# TeensyAmp_R4_0.net
KiCad netlist of a schematic drawn in EAGLE
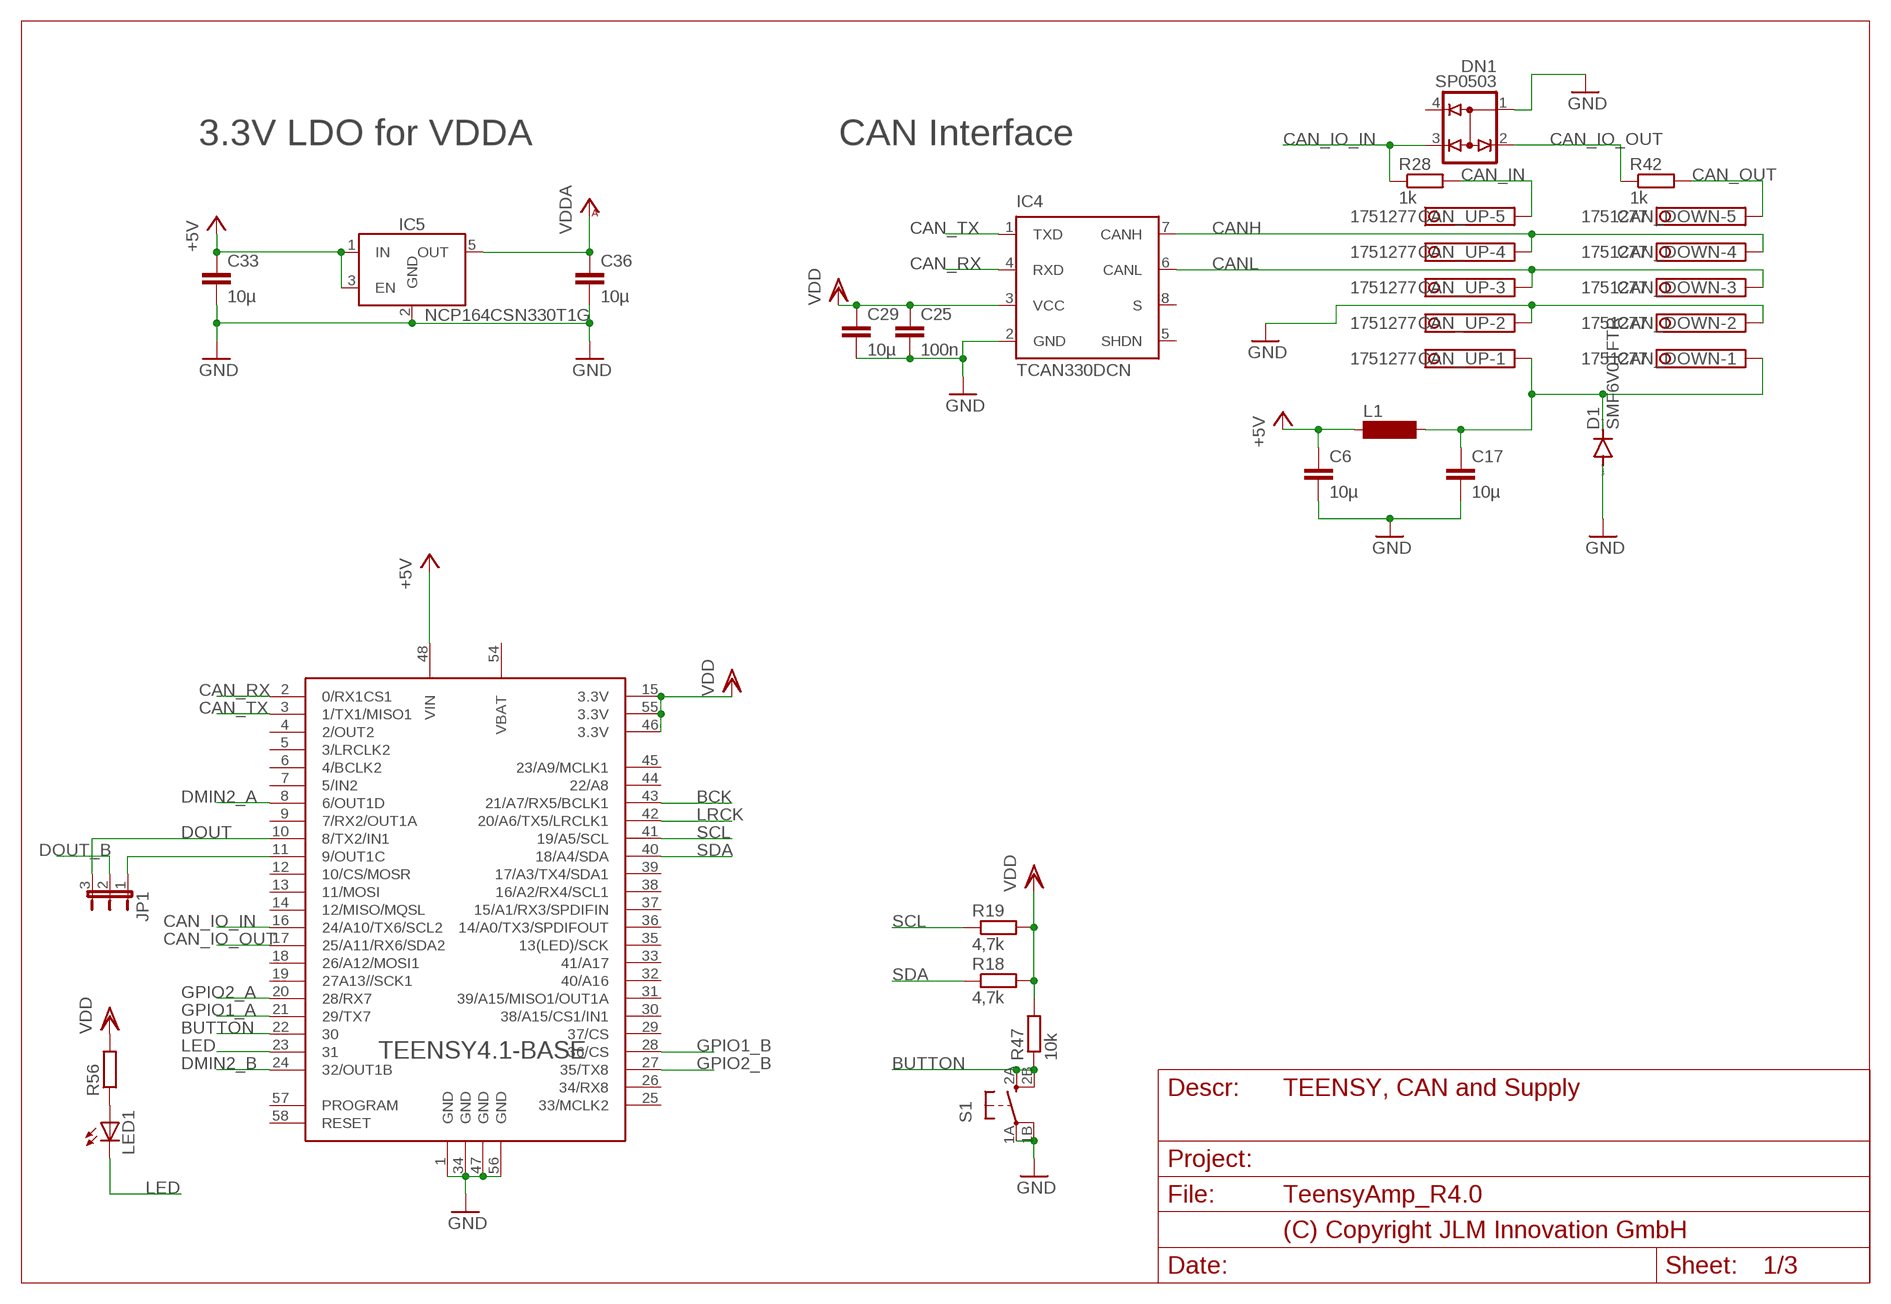
[diagram p0: schematic, sheet 1]
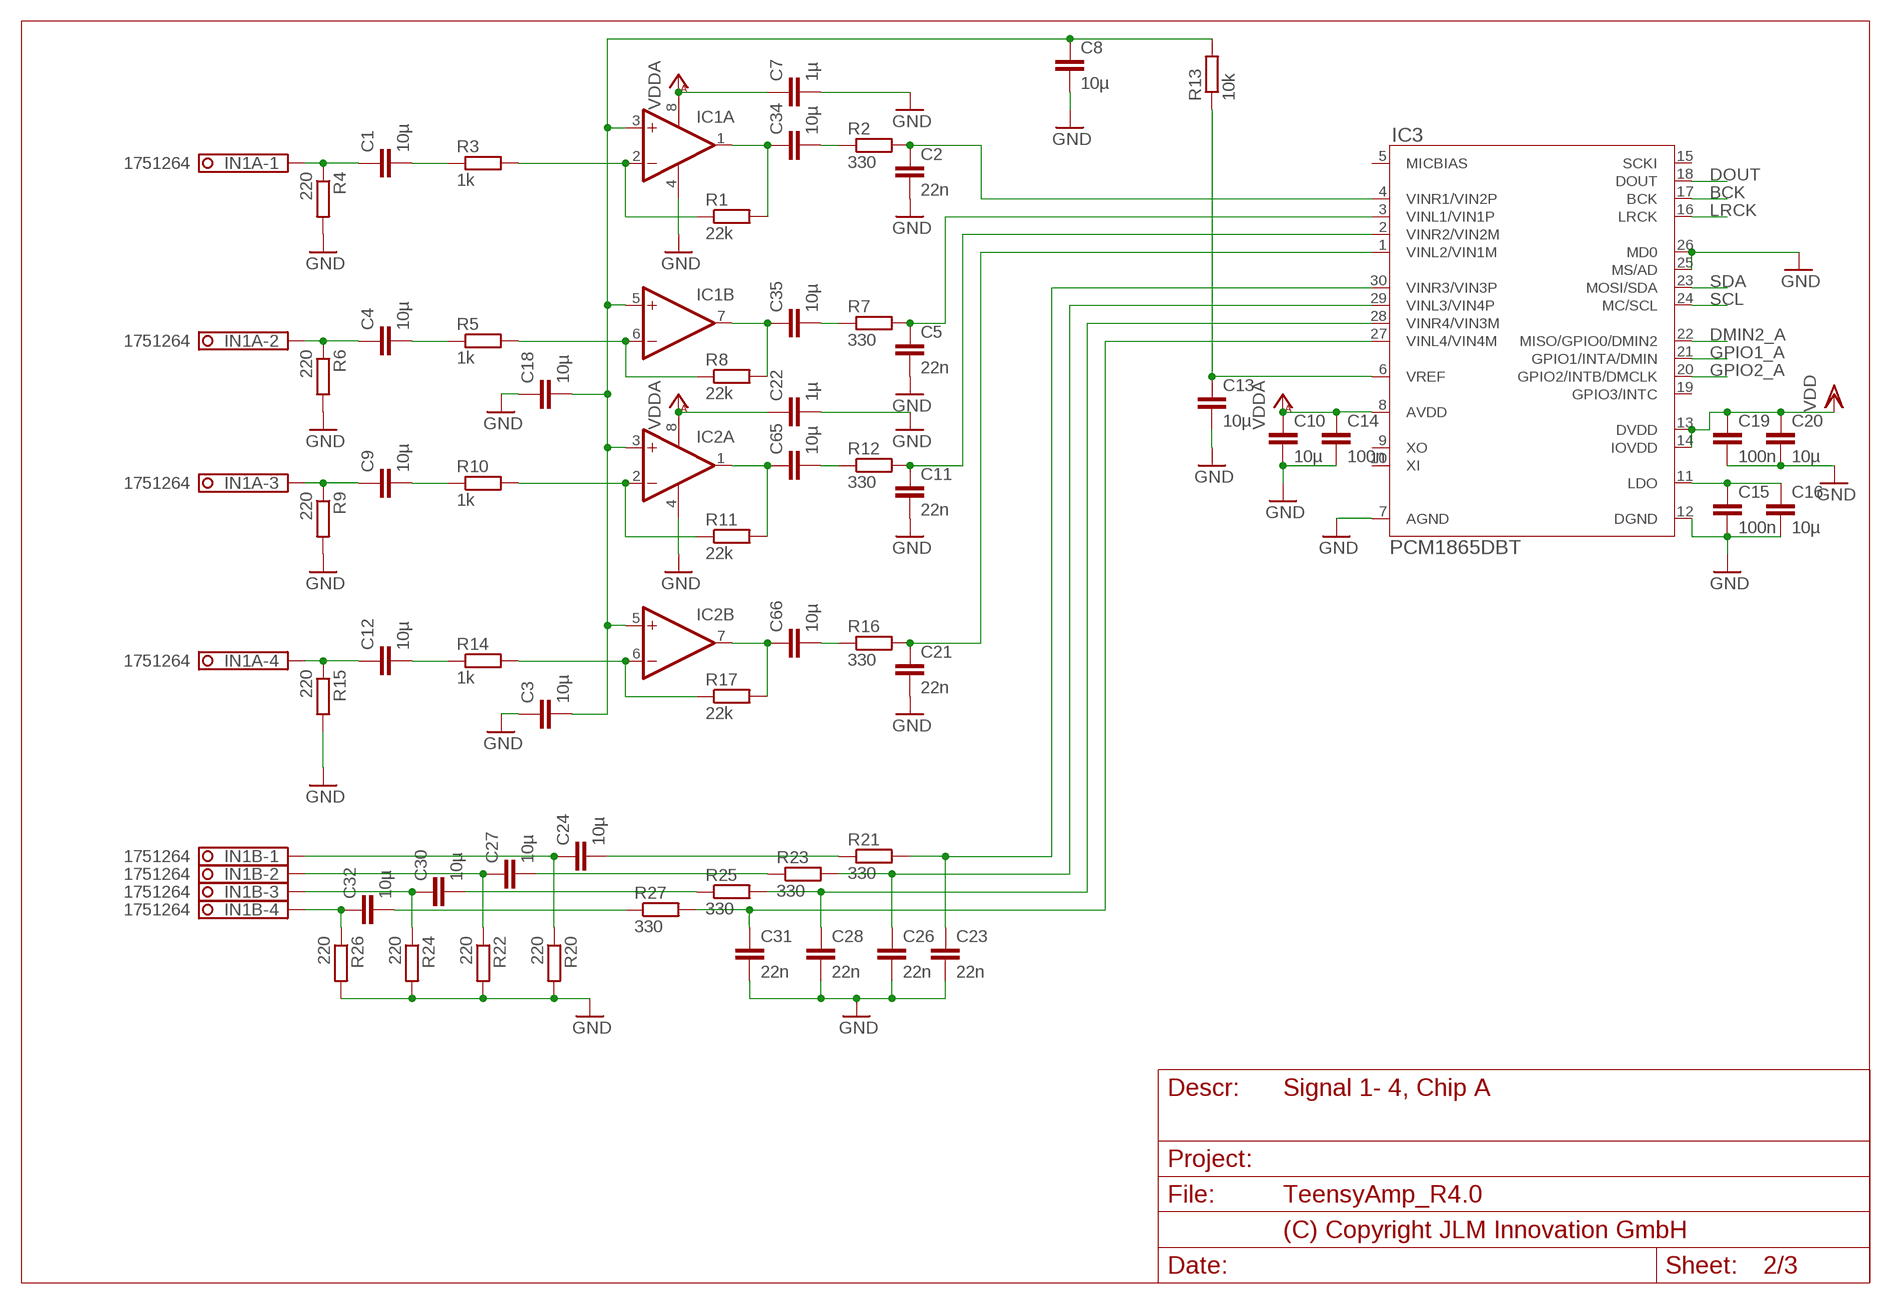
[diagram p1: schematic, sheet 2]
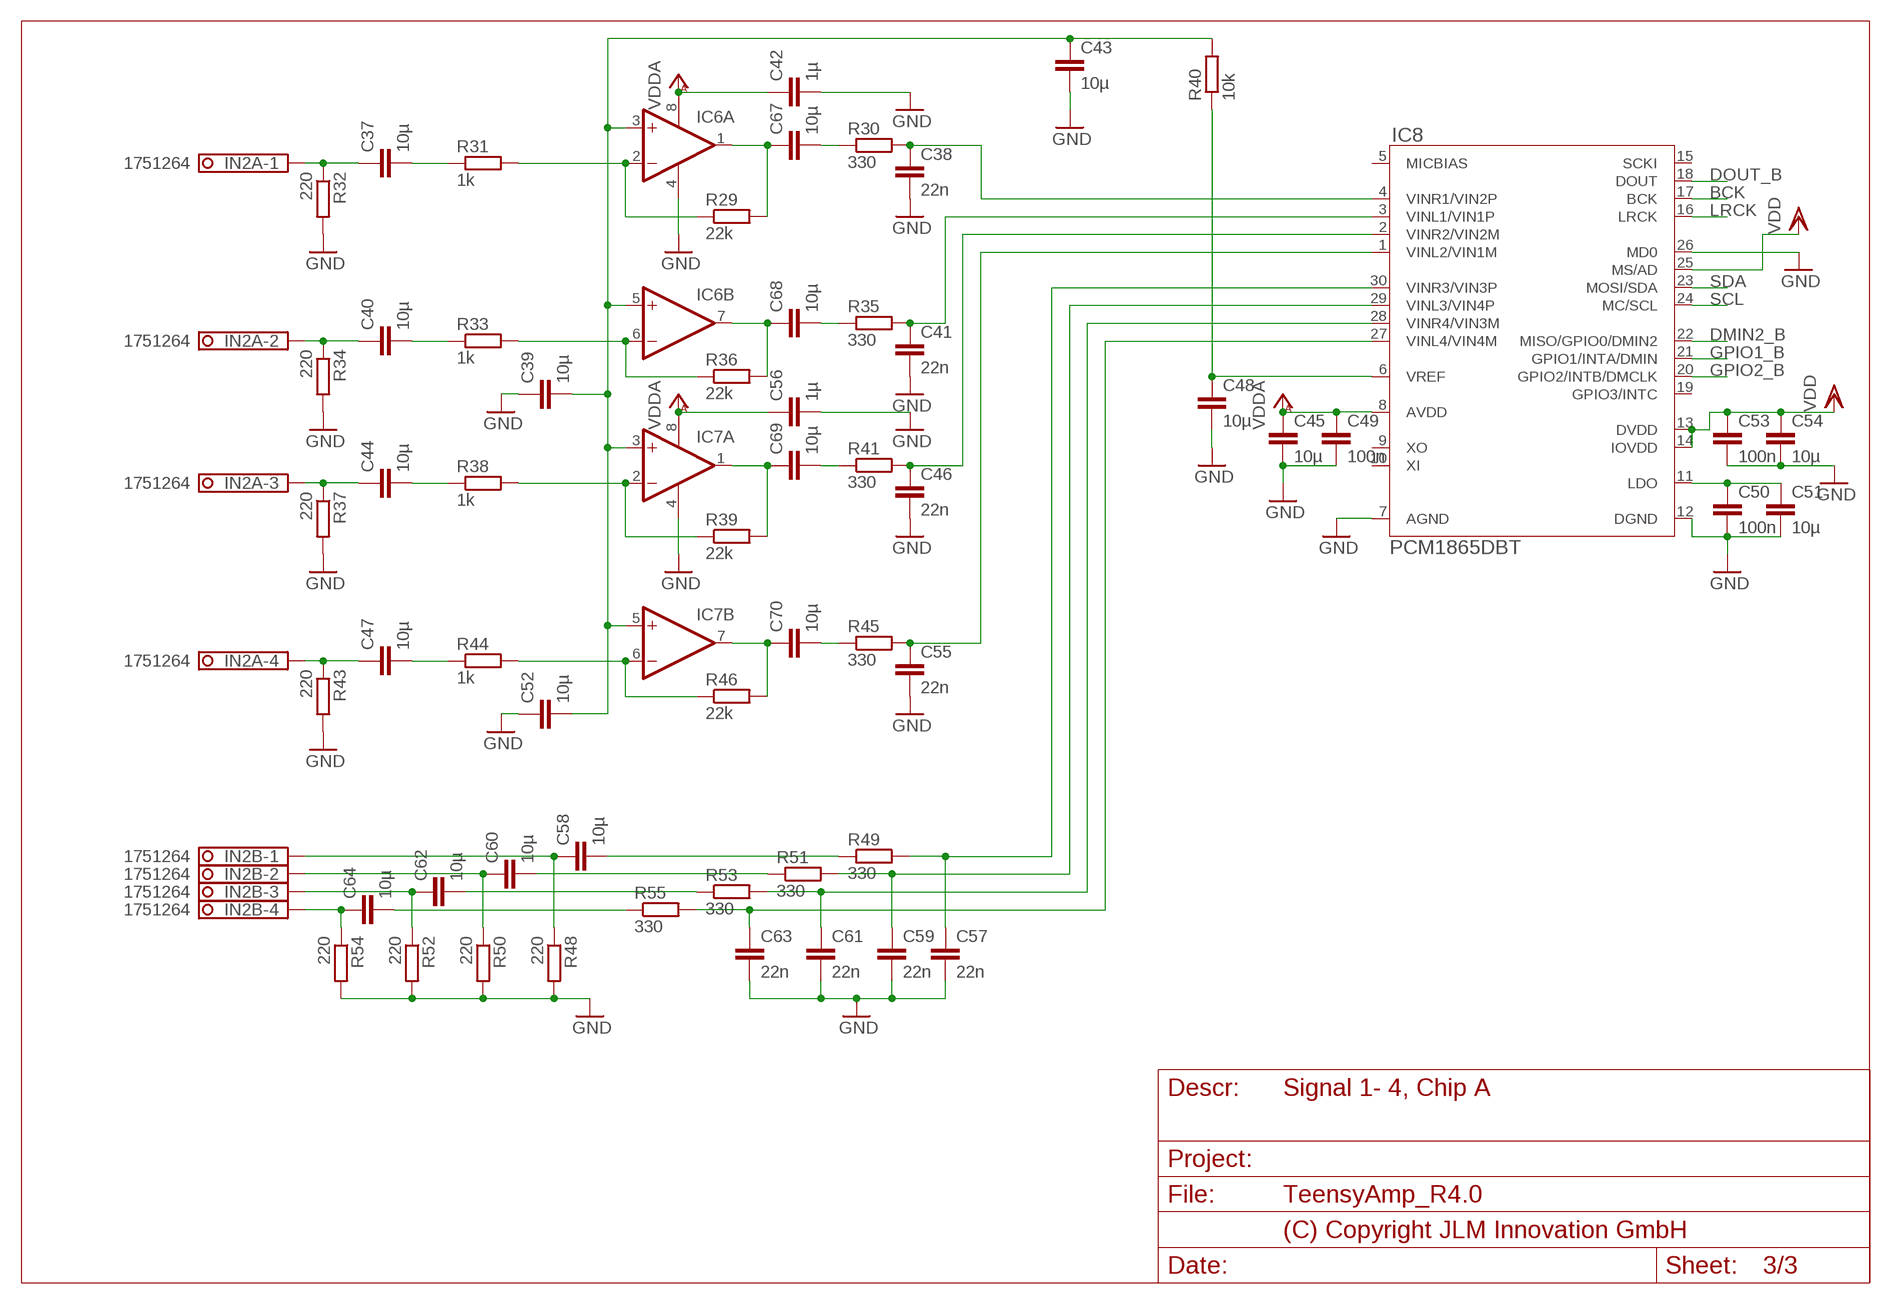
[diagram p2: schematic, sheet 3]

(export (version "E")
  (design (tool "Eeschema 10.0.6"))
  (components
    (comp (ref "C6")
      (value "10µ")
      (footprint "eagle-import:C0805")
      (libsource (lib "eagle-import") (part "C-EUC0805"))
    )
    (comp (ref "C17")
      (value "10µ")
      (footprint "eagle-import:C0805")
      (libsource (lib "eagle-import") (part "C-EUC0805"))
    )
    (comp (ref "C25")
      (value "100n")
      (footprint "eagle-import:0402-N")
      (libsource (lib "eagle-import") (part "C-EU0402-NARROW"))
    )
    (comp (ref "C29")
      (value "10µ")
      (footprint "eagle-import:C0603")
      (libsource (lib "eagle-import") (part "C-EUC0603"))
    )
    (comp (ref "C33")
      (value "10µ")
      (footprint "eagle-import:C0603")
      (libsource (lib "eagle-import") (part "C-EUC0603"))
    )
    (comp (ref "C36")
      (value "10µ")
      (footprint "eagle-import:C0603")
      (libsource (lib "eagle-import") (part "C-EUC0603"))
    )
    (comp (ref "CAN_DOWN")
      (value "1751277")
      (footprint "eagle-import:1751277")
      (libsource (lib "eagle-import") (part "1751277"))
    )
    (comp (ref "CAN_UP")
      (value "1751277")
      (footprint "eagle-import:1751277")
      (libsource (lib "eagle-import") (part "1751277"))
    )
    (comp (ref "D1")
      (value "SMF6V0TFTR")
      (footprint "eagle-import:SOD123")
      (libsource (lib "eagle-import") (part "DIODE-SOD123"))
    )
    (comp (ref "DN1")
      (value "SP0503")
      (footprint "eagle-import:SOT143-R")
      (fields (field (name "OC_FARNELL") "1827633"))
      (libsource (lib "eagle-import") (part "SP0503"))
    )
    (comp (ref "IC4")
      (value "TCAN330DCN")
      (footprint "eagle-import:SOT65P280X145-8N")
      (libsource (lib "eagle-import") (part "TCAN330DCN"))
    )
    (comp (ref "IC5")
      (value "NCP164CSN330T1G")
      (footprint "eagle-import:SOT23-5")
      (libsource (lib "eagle-import") (part "LDO_ENSOT23-5"))
    )
    (comp (ref "JP1")
      (value "JP2E")
      (footprint "eagle-import:JP2")
      (libsource (lib "eagle-import") (part "JP2E"))
    )
    (comp (ref "L1")
      (value "L_JLM0805")
      (footprint "eagle-import:R0805")
      (libsource (lib "eagle-import") (part "L_JLM0805"))
    )
    (comp (ref "LED1")
      (value "LEDCHIP-LED0603")
      (footprint "eagle-import:CHIP-LED0603")
      (libsource (lib "eagle-import") (part "LEDCHIP-LED0603"))
    )
    (comp (ref "R18")
      (value "4,7k")
      (footprint "eagle-import:R0402")
      (libsource (lib "eagle-import") (part "R_JLMR0402"))
    )
    (comp (ref "R19")
      (value "4,7k")
      (footprint "eagle-import:R0402")
      (libsource (lib "eagle-import") (part "R_JLMR0402"))
    )
    (comp (ref "R28")
      (value "1k")
      (footprint "eagle-import:0402-N")
      (libsource (lib "eagle-import") (part "R_JLM0402-NARROW"))
    )
    (comp (ref "R42")
      (value "1k")
      (footprint "eagle-import:0402-N")
      (libsource (lib "eagle-import") (part "R_JLM0402-NARROW"))
    )
    (comp (ref "R47")
      (value "10k")
      (footprint "eagle-import:R0402")
      (libsource (lib "eagle-import") (part "R_JLMR0402"))
    )
    (comp (ref "R56")
      (value "R_JLMR0402")
      (footprint "eagle-import:R0402")
      (libsource (lib "eagle-import") (part "R_JLMR0402"))
    )
    (comp (ref "S1")
      (value "SWITCH7914")
      (footprint "eagle-import:7914J")
      (libsource (lib "eagle-import") (part "SWITCH7914"))
    )
    (comp (ref "TEENSY4.1")
      (value "TEENSY4.1")
      (footprint "eagle-import:TEENSY4.1")
      (libsource (lib "eagle-import") (part "TEENSY4.1"))
    )
    (comp (ref "C37")
      (value "10µ")
      (footprint "eagle-import:C0805")
      (libsource (lib "eagle-import") (part "C-EUC0805"))
    )
    (comp (ref "C38")
      (value "22n")
      (footprint "eagle-import:C0603")
      (libsource (lib "eagle-import") (part "C-EUC0603"))
    )
    (comp (ref "C39")
      (value "10µ")
      (footprint "eagle-import:C0603")
      (libsource (lib "eagle-import") (part "C-EUC0603"))
    )
    (comp (ref "C40")
      (value "10µ")
      (footprint "eagle-import:C0805")
      (libsource (lib "eagle-import") (part "C-EUC0805"))
    )
    (comp (ref "C41")
      (value "22n")
      (footprint "eagle-import:C0603")
      (libsource (lib "eagle-import") (part "C-EUC0603"))
    )
    (comp (ref "C42")
      (value "1µ")
      (footprint "eagle-import:C0603")
      (libsource (lib "eagle-import") (part "C-EUC0603"))
    )
    (comp (ref "C43")
      (value "10µ")
      (footprint "eagle-import:C0603")
      (libsource (lib "eagle-import") (part "C-EUC0603"))
    )
    (comp (ref "C44")
      (value "10µ")
      (footprint "eagle-import:C0805")
      (libsource (lib "eagle-import") (part "C-EUC0805"))
    )
    (comp (ref "C45")
      (value "10µ")
      (footprint "eagle-import:C0603")
      (libsource (lib "eagle-import") (part "C-EUC0603"))
    )
    (comp (ref "C46")
      (value "22n")
      (footprint "eagle-import:C0603")
      (libsource (lib "eagle-import") (part "C-EUC0603"))
    )
    (comp (ref "C47")
      (value "10µ")
      (footprint "eagle-import:C0805")
      (libsource (lib "eagle-import") (part "C-EUC0805"))
    )
    (comp (ref "C48")
      (value "10µ")
      (footprint "eagle-import:C0603")
      (libsource (lib "eagle-import") (part "C-EUC0603"))
    )
    (comp (ref "C49")
      (value "100n")
      (footprint "eagle-import:0402-N")
      (libsource (lib "eagle-import") (part "C-EU0402-NARROW"))
    )
    (comp (ref "C50")
      (value "100n")
      (footprint "eagle-import:0402-N")
      (libsource (lib "eagle-import") (part "C-EU0402-NARROW"))
    )
    (comp (ref "C51")
      (value "10µ")
      (footprint "eagle-import:C0603")
      (libsource (lib "eagle-import") (part "C-EUC0603"))
    )
    (comp (ref "C52")
      (value "10µ")
      (footprint "eagle-import:C0603")
      (libsource (lib "eagle-import") (part "C-EUC0603"))
    )
    (comp (ref "C53")
      (value "100n")
      (footprint "eagle-import:0402-N")
      (libsource (lib "eagle-import") (part "C-EU0402-NARROW"))
    )
    (comp (ref "C54")
      (value "10µ")
      (footprint "eagle-import:C0603")
      (libsource (lib "eagle-import") (part "C-EUC0603"))
    )
    (comp (ref "C55")
      (value "22n")
      (footprint "eagle-import:C0603")
      (libsource (lib "eagle-import") (part "C-EUC0603"))
    )
    (comp (ref "C56")
      (value "1µ")
      (footprint "eagle-import:C0603")
      (libsource (lib "eagle-import") (part "C-EUC0603"))
    )
    (comp (ref "C57")
      (value "22n")
      (footprint "eagle-import:C0603")
      (libsource (lib "eagle-import") (part "C-EUC0603"))
    )
    (comp (ref "C58")
      (value "10µ")
      (footprint "eagle-import:C0805")
      (libsource (lib "eagle-import") (part "C-EUC0805"))
    )
    (comp (ref "C59")
      (value "22n")
      (footprint "eagle-import:C0603")
      (libsource (lib "eagle-import") (part "C-EUC0603"))
    )
    (comp (ref "C60")
      (value "10µ")
      (footprint "eagle-import:C0805")
      (libsource (lib "eagle-import") (part "C-EUC0805"))
    )
    (comp (ref "C61")
      (value "22n")
      (footprint "eagle-import:C0603")
      (libsource (lib "eagle-import") (part "C-EUC0603"))
    )
    (comp (ref "C62")
      (value "10µ")
      (footprint "eagle-import:C0805")
      (libsource (lib "eagle-import") (part "C-EUC0805"))
    )
    (comp (ref "C63")
      (value "22n")
      (footprint "eagle-import:C0603")
      (libsource (lib "eagle-import") (part "C-EUC0603"))
    )
    (comp (ref "C64")
      (value "10µ")
      (footprint "eagle-import:C0805")
      (libsource (lib "eagle-import") (part "C-EUC0805"))
    )
    (comp (ref "C67")
      (value "10µ")
      (footprint "eagle-import:C0805")
      (libsource (lib "eagle-import") (part "C-EUC0805"))
    )
    (comp (ref "C68")
      (value "10µ")
      (footprint "eagle-import:C0805")
      (libsource (lib "eagle-import") (part "C-EUC0805"))
    )
    (comp (ref "C69")
      (value "10µ")
      (footprint "eagle-import:C0805")
      (libsource (lib "eagle-import") (part "C-EUC0805"))
    )
    (comp (ref "C70")
      (value "10µ")
      (footprint "eagle-import:C0805")
      (libsource (lib "eagle-import") (part "C-EUC0805"))
    )
    (comp (ref "IC6")
      (value "OPA2344E")
      (footprint "eagle-import:MSOP08")
      (libsource (lib "eagle-import") (part "OPA2E344"))
    )
    (comp (ref "IC7")
      (value "OPA2344E")
      (footprint "eagle-import:MSOP08")
      (libsource (lib "eagle-import") (part "OPA2E344"))
    )
    (comp (ref "IC8")
      (value "PCM1865DBT")
      (footprint "eagle-import:SOP50P640X120-30N")
      (libsource (lib "eagle-import") (part "PCM1865DBT"))
    )
    (comp (ref "IN2A")
      (value "1751264")
      (footprint "eagle-import:1751264")
      (libsource (lib "eagle-import") (part "1751264"))
    )
    (comp (ref "IN2B")
      (value "1751264")
      (footprint "eagle-import:1751264")
      (libsource (lib "eagle-import") (part "1751264"))
    )
    (comp (ref "R29")
      (value "22k")
      (footprint "eagle-import:R0603")
      (libsource (lib "eagle-import") (part "R_JLMR0603"))
    )
    (comp (ref "R30")
      (value "330")
      (footprint "eagle-import:R0603")
      (libsource (lib "eagle-import") (part "R_JLMR0603"))
    )
    (comp (ref "R31")
      (value "1k")
      (footprint "eagle-import:R0603")
      (libsource (lib "eagle-import") (part "R_JLMR0603"))
    )
    (comp (ref "R32")
      (value "220")
      (footprint "eagle-import:R0603")
      (libsource (lib "eagle-import") (part "R_JLMR0603"))
    )
    (comp (ref "R33")
      (value "1k")
      (footprint "eagle-import:R0603")
      (libsource (lib "eagle-import") (part "R_JLMR0603"))
    )
    (comp (ref "R34")
      (value "220")
      (footprint "eagle-import:R0603")
      (libsource (lib "eagle-import") (part "R_JLMR0603"))
    )
    (comp (ref "R35")
      (value "330")
      (footprint "eagle-import:R0603")
      (libsource (lib "eagle-import") (part "R_JLMR0603"))
    )
    (comp (ref "R36")
      (value "22k")
      (footprint "eagle-import:R0603")
      (libsource (lib "eagle-import") (part "R_JLMR0603"))
    )
    (comp (ref "R37")
      (value "220")
      (footprint "eagle-import:R0603")
      (libsource (lib "eagle-import") (part "R_JLMR0603"))
    )
    (comp (ref "R38")
      (value "1k")
      (footprint "eagle-import:R0603")
      (libsource (lib "eagle-import") (part "R_JLMR0603"))
    )
    (comp (ref "R39")
      (value "22k")
      (footprint "eagle-import:R0603")
      (libsource (lib "eagle-import") (part "R_JLMR0603"))
    )
    (comp (ref "R40")
      (value "10k")
      (footprint "eagle-import:0402-N")
      (libsource (lib "eagle-import") (part "R_JLM0402-NARROW"))
    )
    (comp (ref "R41")
      (value "330")
      (footprint "eagle-import:R0603")
      (libsource (lib "eagle-import") (part "R_JLMR0603"))
    )
    (comp (ref "R43")
      (value "220")
      (footprint "eagle-import:R0603")
      (libsource (lib "eagle-import") (part "R_JLMR0603"))
    )
    (comp (ref "R44")
      (value "1k")
      (footprint "eagle-import:R0603")
      (libsource (lib "eagle-import") (part "R_JLMR0603"))
    )
    (comp (ref "R45")
      (value "330")
      (footprint "eagle-import:R0603")
      (libsource (lib "eagle-import") (part "R_JLMR0603"))
    )
    (comp (ref "R46")
      (value "22k")
      (footprint "eagle-import:R0603")
      (libsource (lib "eagle-import") (part "R_JLMR0603"))
    )
    (comp (ref "R48")
      (value "220")
      (footprint "eagle-import:R0603")
      (libsource (lib "eagle-import") (part "R_JLMR0603"))
    )
    (comp (ref "R49")
      (value "330")
      (footprint "eagle-import:R0603")
      (libsource (lib "eagle-import") (part "R_JLMR0603"))
    )
    (comp (ref "R50")
      (value "220")
      (footprint "eagle-import:R0603")
      (libsource (lib "eagle-import") (part "R_JLMR0603"))
    )
    (comp (ref "R51")
      (value "330")
      (footprint "eagle-import:R0603")
      (libsource (lib "eagle-import") (part "R_JLMR0603"))
    )
    (comp (ref "R52")
      (value "220")
      (footprint "eagle-import:R0603")
      (libsource (lib "eagle-import") (part "R_JLMR0603"))
    )
    (comp (ref "R53")
      (value "330")
      (footprint "eagle-import:R0603")
      (libsource (lib "eagle-import") (part "R_JLMR0603"))
    )
    (comp (ref "R54")
      (value "220")
      (footprint "eagle-import:R0603")
      (libsource (lib "eagle-import") (part "R_JLMR0603"))
    )
    (comp (ref "R55")
      (value "330")
      (footprint "eagle-import:R0603")
      (libsource (lib "eagle-import") (part "R_JLMR0603"))
    )
    (comp (ref "C1")
      (value "10µ")
      (footprint "eagle-import:C0805")
      (libsource (lib "eagle-import") (part "C-EUC0805"))
    )
    (comp (ref "C2")
      (value "22n")
      (footprint "eagle-import:C0603")
      (libsource (lib "eagle-import") (part "C-EUC0603"))
    )
    (comp (ref "C3")
      (value "10µ")
      (footprint "eagle-import:C0603")
      (libsource (lib "eagle-import") (part "C-EUC0603"))
    )
    (comp (ref "C4")
      (value "10µ")
      (footprint "eagle-import:C0805")
      (libsource (lib "eagle-import") (part "C-EUC0805"))
    )
    (comp (ref "C5")
      (value "22n")
      (footprint "eagle-import:C0603")
      (libsource (lib "eagle-import") (part "C-EUC0603"))
    )
    (comp (ref "C7")
      (value "1µ")
      (footprint "eagle-import:C0603")
      (libsource (lib "eagle-import") (part "C-EUC0603"))
    )
    (comp (ref "C8")
      (value "10µ")
      (footprint "eagle-import:C0603")
      (libsource (lib "eagle-import") (part "C-EUC0603"))
    )
    (comp (ref "C9")
      (value "10µ")
      (footprint "eagle-import:C0805")
      (libsource (lib "eagle-import") (part "C-EUC0805"))
    )
    (comp (ref "C10")
      (value "10µ")
      (footprint "eagle-import:C0603")
      (libsource (lib "eagle-import") (part "C-EUC0603"))
    )
    (comp (ref "C11")
      (value "22n")
      (footprint "eagle-import:C0603")
      (libsource (lib "eagle-import") (part "C-EUC0603"))
    )
    (comp (ref "C12")
      (value "10µ")
      (footprint "eagle-import:C0805")
      (libsource (lib "eagle-import") (part "C-EUC0805"))
    )
    (comp (ref "C13")
      (value "10µ")
      (footprint "eagle-import:C0603")
      (libsource (lib "eagle-import") (part "C-EUC0603"))
    )
    (comp (ref "C14")
      (value "100n")
      (footprint "eagle-import:0402-N")
      (libsource (lib "eagle-import") (part "C-EU0402-NARROW"))
    )
    (comp (ref "C15")
      (value "100n")
      (footprint "eagle-import:0402-N")
      (libsource (lib "eagle-import") (part "C-EU0402-NARROW"))
    )
    (comp (ref "C16")
      (value "10µ")
      (footprint "eagle-import:C0603")
      (libsource (lib "eagle-import") (part "C-EUC0603"))
    )
    (comp (ref "C18")
      (value "10µ")
      (footprint "eagle-import:C0603")
      (libsource (lib "eagle-import") (part "C-EUC0603"))
    )
    (comp (ref "C19")
      (value "100n")
      (footprint "eagle-import:0402-N")
      (libsource (lib "eagle-import") (part "C-EU0402-NARROW"))
    )
    (comp (ref "C20")
      (value "10µ")
      (footprint "eagle-import:C0603")
      (libsource (lib "eagle-import") (part "C-EUC0603"))
    )
    (comp (ref "C21")
      (value "22n")
      (footprint "eagle-import:C0603")
      (libsource (lib "eagle-import") (part "C-EUC0603"))
    )
    (comp (ref "C22")
      (value "1µ")
      (footprint "eagle-import:C0603")
      (libsource (lib "eagle-import") (part "C-EUC0603"))
    )
    (comp (ref "C23")
      (value "22n")
      (footprint "eagle-import:C0603")
      (libsource (lib "eagle-import") (part "C-EUC0603"))
    )
    (comp (ref "C24")
      (value "10µ")
      (footprint "eagle-import:C0805")
      (libsource (lib "eagle-import") (part "C-EUC0805"))
    )
    (comp (ref "C26")
      (value "22n")
      (footprint "eagle-import:C0603")
      (libsource (lib "eagle-import") (part "C-EUC0603"))
    )
    (comp (ref "C27")
      (value "10µ")
      (footprint "eagle-import:C0805")
      (libsource (lib "eagle-import") (part "C-EUC0805"))
    )
    (comp (ref "C28")
      (value "22n")
      (footprint "eagle-import:C0603")
      (libsource (lib "eagle-import") (part "C-EUC0603"))
    )
    (comp (ref "C30")
      (value "10µ")
      (footprint "eagle-import:C0805")
      (libsource (lib "eagle-import") (part "C-EUC0805"))
    )
    (comp (ref "C31")
      (value "22n")
      (footprint "eagle-import:C0603")
      (libsource (lib "eagle-import") (part "C-EUC0603"))
    )
    (comp (ref "C32")
      (value "10µ")
      (footprint "eagle-import:C0805")
      (libsource (lib "eagle-import") (part "C-EUC0805"))
    )
    (comp (ref "C34")
      (value "10µ")
      (footprint "eagle-import:C0805")
      (libsource (lib "eagle-import") (part "C-EUC0805"))
    )
    (comp (ref "C35")
      (value "10µ")
      (footprint "eagle-import:C0805")
      (libsource (lib "eagle-import") (part "C-EUC0805"))
    )
    (comp (ref "C65")
      (value "10µ")
      (footprint "eagle-import:C0805")
      (libsource (lib "eagle-import") (part "C-EUC0805"))
    )
    (comp (ref "C66")
      (value "10µ")
      (footprint "eagle-import:C0805")
      (libsource (lib "eagle-import") (part "C-EUC0805"))
    )
    (comp (ref "IC1")
      (value "OPA2344E")
      (footprint "eagle-import:MSOP08")
      (libsource (lib "eagle-import") (part "OPA2E344"))
    )
    (comp (ref "IC2")
      (value "OPA2344E")
      (footprint "eagle-import:MSOP08")
      (libsource (lib "eagle-import") (part "OPA2E344"))
    )
    (comp (ref "IC3")
      (value "PCM1865DBT")
      (footprint "eagle-import:SOP50P640X120-30N")
      (libsource (lib "eagle-import") (part "PCM1865DBT"))
    )
    (comp (ref "IN1A")
      (value "1751264")
      (footprint "eagle-import:1751264")
      (libsource (lib "eagle-import") (part "1751264"))
    )
    (comp (ref "IN1B")
      (value "1751264")
      (footprint "eagle-import:1751264")
      (libsource (lib "eagle-import") (part "1751264"))
    )
    (comp (ref "R1")
      (value "22k")
      (footprint "eagle-import:R0603")
      (libsource (lib "eagle-import") (part "R_JLMR0603"))
    )
    (comp (ref "R2")
      (value "330")
      (footprint "eagle-import:R0603")
      (libsource (lib "eagle-import") (part "R_JLMR0603"))
    )
    (comp (ref "R3")
      (value "1k")
      (footprint "eagle-import:R0603")
      (libsource (lib "eagle-import") (part "R_JLMR0603"))
    )
    (comp (ref "R4")
      (value "220")
      (footprint "eagle-import:R0603")
      (libsource (lib "eagle-import") (part "R_JLMR0603"))
    )
    (comp (ref "R5")
      (value "1k")
      (footprint "eagle-import:R0603")
      (libsource (lib "eagle-import") (part "R_JLMR0603"))
    )
    (comp (ref "R6")
      (value "220")
      (footprint "eagle-import:R0603")
      (libsource (lib "eagle-import") (part "R_JLMR0603"))
    )
    (comp (ref "R7")
      (value "330")
      (footprint "eagle-import:R0603")
      (libsource (lib "eagle-import") (part "R_JLMR0603"))
    )
    (comp (ref "R8")
      (value "22k")
      (footprint "eagle-import:R0603")
      (libsource (lib "eagle-import") (part "R_JLMR0603"))
    )
    (comp (ref "R9")
      (value "220")
      (footprint "eagle-import:R0603")
      (libsource (lib "eagle-import") (part "R_JLMR0603"))
    )
    (comp (ref "R10")
      (value "1k")
      (footprint "eagle-import:R0603")
      (libsource (lib "eagle-import") (part "R_JLMR0603"))
    )
    (comp (ref "R11")
      (value "22k")
      (footprint "eagle-import:R0603")
      (libsource (lib "eagle-import") (part "R_JLMR0603"))
    )
    (comp (ref "R12")
      (value "330")
      (footprint "eagle-import:R0603")
      (libsource (lib "eagle-import") (part "R_JLMR0603"))
    )
    (comp (ref "R13")
      (value "10k")
      (footprint "eagle-import:0402-N")
      (libsource (lib "eagle-import") (part "R_JLM0402-NARROW"))
    )
    (comp (ref "R14")
      (value "1k")
      (footprint "eagle-import:R0603")
      (libsource (lib "eagle-import") (part "R_JLMR0603"))
    )
    (comp (ref "R15")
      (value "220")
      (footprint "eagle-import:R0603")
      (libsource (lib "eagle-import") (part "R_JLMR0603"))
    )
    (comp (ref "R16")
      (value "330")
      (footprint "eagle-import:R0603")
      (libsource (lib "eagle-import") (part "R_JLMR0603"))
    )
    (comp (ref "R17")
      (value "22k")
      (footprint "eagle-import:R0603")
      (libsource (lib "eagle-import") (part "R_JLMR0603"))
    )
    (comp (ref "R20")
      (value "220")
      (footprint "eagle-import:R0603")
      (libsource (lib "eagle-import") (part "R_JLMR0603"))
    )
    (comp (ref "R21")
      (value "330")
      (footprint "eagle-import:R0603")
      (libsource (lib "eagle-import") (part "R_JLMR0603"))
    )
    (comp (ref "R22")
      (value "220")
      (footprint "eagle-import:R0603")
      (libsource (lib "eagle-import") (part "R_JLMR0603"))
    )
    (comp (ref "R23")
      (value "330")
      (footprint "eagle-import:R0603")
      (libsource (lib "eagle-import") (part "R_JLMR0603"))
    )
    (comp (ref "R24")
      (value "220")
      (footprint "eagle-import:R0603")
      (libsource (lib "eagle-import") (part "R_JLMR0603"))
    )
    (comp (ref "R25")
      (value "330")
      (footprint "eagle-import:R0603")
      (libsource (lib "eagle-import") (part "R_JLMR0603"))
    )
    (comp (ref "R26")
      (value "220")
      (footprint "eagle-import:R0603")
      (libsource (lib "eagle-import") (part "R_JLMR0603"))
    )
    (comp (ref "R27")
      (value "330")
      (footprint "eagle-import:R0603")
      (libsource (lib "eagle-import") (part "R_JLMR0603"))
    )
  )
  (nets
    (net (code "1") (name "+5V") (class "Default")
      (node (ref "C33") (pin "1") (pinfunction "1_1") (pintype "passive"))
      (node (ref "C6") (pin "1") (pinfunction "1_1") (pintype "passive"))
      (node (ref "IC5") (pin "1") (pinfunction "IN_1") (pintype "input"))
      (node (ref "IC5") (pin "3") (pinfunction "EN_3") (pintype "input"))
      (node (ref "L1") (pin "1") (pinfunction "1_1") (pintype "passive"))
      (node (ref "TEENSY4.1") (pin "48") (pinfunction "VIN_48") (pintype "power_in"))
    )
    (net (code "2") (name "BCK") (class "Default")
      (node (ref "IC3") (pin "17") (pinfunction "BCK_17") (pintype "bidirectional"))
      (node (ref "IC8") (pin "17") (pinfunction "BCK_17") (pintype "bidirectional"))
      (node (ref "TEENSY4.1") (pin "43") (pinfunction "21/A7/RX5/BCLK1_43") (pintype "bidirectional"))
    )
    (net (code "3") (name "BUTTON") (class "Default")
      (node (ref "R47") (pin "1") (pinfunction "1_1") (pintype "passive"))
      (node (ref "S1") (pin "2A") (pinfunction "S_2A") (pintype "passive"))
      (node (ref "S1") (pin "2B") (pinfunction "S1_2B") (pintype "passive"))
      (node (ref "TEENSY4.1") (pin "22") (pinfunction "30_22") (pintype "bidirectional"))
    )
    (net (code "4") (name "CANH") (class "Default")
      (node (ref "CAN_DOWN") (pin "4") (pinfunction "K_4") (pintype "passive"))
      (node (ref "CAN_UP") (pin "4") (pinfunction "K_4") (pintype "passive"))
      (node (ref "IC4") (pin "7") (pinfunction "CANH_7") (pintype "passive"))
    )
    (net (code "5") (name "CANL") (class "Default")
      (node (ref "CAN_DOWN") (pin "3") (pinfunction "K_3") (pintype "passive"))
      (node (ref "CAN_UP") (pin "3") (pinfunction "K_3") (pintype "passive"))
      (node (ref "IC4") (pin "6") (pinfunction "CANL_6") (pintype "passive"))
    )
    (net (code "6") (name "CAN_IN") (class "Default")
      (node (ref "CAN_UP") (pin "5") (pinfunction "K_5") (pintype "passive"))
      (node (ref "R28") (pin "2") (pinfunction "2_2") (pintype "passive"))
    )
    (net (code "7") (name "CAN_IO_IN") (class "Default")
      (node (ref "DN1") (pin "3") (pinfunction "C3_3") (pintype "passive"))
      (node (ref "R28") (pin "1") (pinfunction "1_1") (pintype "passive"))
      (node (ref "TEENSY4.1") (pin "16") (pinfunction "24/A10/TX6/SCL2_16") (pintype "bidirectional"))
    )
    (net (code "8") (name "CAN_IO_OUT") (class "Default")
      (node (ref "DN1") (pin "2") (pinfunction "C2_2") (pintype "passive"))
      (node (ref "R42") (pin "1") (pinfunction "1_1") (pintype "passive"))
      (node (ref "TEENSY4.1") (pin "17") (pinfunction "25/A11/RX6/SDA2_17") (pintype "bidirectional"))
    )
    (net (code "9") (name "CAN_OUT") (class "Default")
      (node (ref "CAN_DOWN") (pin "5") (pinfunction "K_5") (pintype "passive"))
      (node (ref "R42") (pin "2") (pinfunction "2_2") (pintype "passive"))
    )
    (net (code "10") (name "CAN_RX") (class "Default")
      (node (ref "IC4") (pin "4") (pinfunction "RXD_4") (pintype "output"))
      (node (ref "TEENSY4.1") (pin "2") (pinfunction "0/RX1CS1_2") (pintype "bidirectional"))
    )
    (net (code "11") (name "CAN_TX") (class "Default")
      (node (ref "IC4") (pin "1") (pinfunction "TXD_1") (pintype "input"))
      (node (ref "TEENSY4.1") (pin "3") (pinfunction "1/TX1/MISO1_3") (pintype "bidirectional"))
    )
    (net (code "12") (name "DMIN2_A") (class "Default")
      (node (ref "IC3") (pin "22") (pinfunction "MISO/GPIO0/DMIN2_22") (pintype "bidirectional"))
      (node (ref "TEENSY4.1") (pin "8") (pinfunction "6/OUT1D_8") (pintype "bidirectional"))
    )
    (net (code "13") (name "DMIN2_B") (class "Default")
      (node (ref "IC8") (pin "22") (pinfunction "MISO/GPIO0/DMIN2_22") (pintype "bidirectional"))
      (node (ref "TEENSY4.1") (pin "24") (pinfunction "32/OUT1B_24") (pintype "bidirectional"))
    )
    (net (code "14") (name "DOUT") (class "Default")
      (node (ref "IC3") (pin "18") (pinfunction "DOUT_18") (pintype "output"))
      (node (ref "JP1") (pin "3") (pinfunction "3_3") (pintype "passive"))
      (node (ref "TEENSY4.1") (pin "10") (pinfunction "8/TX2/IN1_10") (pintype "bidirectional"))
    )
    (net (code "15") (name "DOUT_B") (class "Default")
      (node (ref "IC8") (pin "18") (pinfunction "DOUT_18") (pintype "output"))
      (node (ref "JP1") (pin "2") (pinfunction "2_2") (pintype "passive"))
    )
    (net (code "16") (name "GND") (class "Default")
      (node (ref "C10") (pin "2") (pinfunction "2_2") (pintype "passive"))
      (node (ref "C11") (pin "2") (pinfunction "2_2") (pintype "passive"))
      (node (ref "C13") (pin "2") (pinfunction "2_2") (pintype "passive"))
      (node (ref "C14") (pin "2") (pinfunction "2_2") (pintype "passive"))
      (node (ref "C15") (pin "2") (pinfunction "2_2") (pintype "passive"))
      (node (ref "C16") (pin "2") (pinfunction "2_2") (pintype "passive"))
      (node (ref "C17") (pin "2") (pinfunction "2_2") (pintype "passive"))
      (node (ref "C18") (pin "1") (pinfunction "1_1") (pintype "passive"))
      (node (ref "C19") (pin "2") (pinfunction "2_2") (pintype "passive"))
      (node (ref "C2") (pin "2") (pinfunction "2_2") (pintype "passive"))
      (node (ref "C20") (pin "2") (pinfunction "2_2") (pintype "passive"))
      (node (ref "C21") (pin "2") (pinfunction "2_2") (pintype "passive"))
      (node (ref "C22") (pin "2") (pinfunction "2_2") (pintype "passive"))
      (node (ref "C23") (pin "2") (pinfunction "2_2") (pintype "passive"))
      (node (ref "C25") (pin "2") (pinfunction "2_2") (pintype "passive"))
      (node (ref "C26") (pin "2") (pinfunction "2_2") (pintype "passive"))
      (node (ref "C28") (pin "2") (pinfunction "2_2") (pintype "passive"))
      (node (ref "C29") (pin "2") (pinfunction "2_2") (pintype "passive"))
      (node (ref "C3") (pin "1") (pinfunction "1_1") (pintype "passive"))
      (node (ref "C31") (pin "2") (pinfunction "2_2") (pintype "passive"))
      (node (ref "C33") (pin "2") (pinfunction "2_2") (pintype "passive"))
      (node (ref "C36") (pin "2") (pinfunction "2_2") (pintype "passive"))
      (node (ref "C38") (pin "2") (pinfunction "2_2") (pintype "passive"))
      (node (ref "C39") (pin "1") (pinfunction "1_1") (pintype "passive"))
      (node (ref "C41") (pin "2") (pinfunction "2_2") (pintype "passive"))
      (node (ref "C42") (pin "2") (pinfunction "2_2") (pintype "passive"))
      (node (ref "C43") (pin "2") (pinfunction "2_2") (pintype "passive"))
      (node (ref "C45") (pin "2") (pinfunction "2_2") (pintype "passive"))
      (node (ref "C46") (pin "2") (pinfunction "2_2") (pintype "passive"))
      (node (ref "C48") (pin "2") (pinfunction "2_2") (pintype "passive"))
      (node (ref "C49") (pin "2") (pinfunction "2_2") (pintype "passive"))
      (node (ref "C5") (pin "2") (pinfunction "2_2") (pintype "passive"))
      (node (ref "C50") (pin "2") (pinfunction "2_2") (pintype "passive"))
      (node (ref "C51") (pin "2") (pinfunction "2_2") (pintype "passive"))
      (node (ref "C52") (pin "1") (pinfunction "1_1") (pintype "passive"))
      (node (ref "C53") (pin "2") (pinfunction "2_2") (pintype "passive"))
      (node (ref "C54") (pin "2") (pinfunction "2_2") (pintype "passive"))
      (node (ref "C55") (pin "2") (pinfunction "2_2") (pintype "passive"))
      (node (ref "C56") (pin "2") (pinfunction "2_2") (pintype "passive"))
      (node (ref "C57") (pin "2") (pinfunction "2_2") (pintype "passive"))
      (node (ref "C59") (pin "2") (pinfunction "2_2") (pintype "passive"))
      (node (ref "C6") (pin "2") (pinfunction "2_2") (pintype "passive"))
      (node (ref "C61") (pin "2") (pinfunction "2_2") (pintype "passive"))
      (node (ref "C63") (pin "2") (pinfunction "2_2") (pintype "passive"))
      (node (ref "C7") (pin "2") (pinfunction "2_2") (pintype "passive"))
      (node (ref "C8") (pin "2") (pinfunction "2_2") (pintype "passive"))
      (node (ref "CAN_DOWN") (pin "2") (pinfunction "K_2") (pintype "passive"))
      (node (ref "CAN_UP") (pin "2") (pinfunction "K_2") (pintype "passive"))
      (node (ref "D1") (pin "A") (pinfunction "A_A") (pintype "passive"))
      (node (ref "DN1") (pin "1") (pinfunction "A1_1") (pintype "passive"))
      (node (ref "IC1") (pin "4") (pinfunction "V-_4") (pintype "power_in"))
      (node (ref "IC2") (pin "4") (pinfunction "V-_4") (pintype "power_in"))
      (node (ref "IC3") (pin "12") (pinfunction "DGND_12") (pintype "power_in"))
      (node (ref "IC3") (pin "25") (pinfunction "MS/AD_25") (pintype "input"))
      (node (ref "IC3") (pin "26") (pinfunction "MD0_26") (pintype "input"))
      (node (ref "IC3") (pin "7") (pinfunction "AGND_7") (pintype "power_in"))
      (node (ref "IC4") (pin "2") (pinfunction "GND_2") (pintype "power_in"))
      (node (ref "IC5") (pin "2") (pinfunction "GND_2") (pintype "power_in"))
      (node (ref "IC6") (pin "4") (pinfunction "V-_4") (pintype "power_in"))
      (node (ref "IC7") (pin "4") (pinfunction "V-_4") (pintype "power_in"))
      (node (ref "IC8") (pin "12") (pinfunction "DGND_12") (pintype "power_in"))
      (node (ref "IC8") (pin "26") (pinfunction "MD0_26") (pintype "input"))
      (node (ref "IC8") (pin "7") (pinfunction "AGND_7") (pintype "power_in"))
      (node (ref "R15") (pin "2") (pinfunction "2_2") (pintype "passive"))
      (node (ref "R20") (pin "2") (pinfunction "2_2") (pintype "passive"))
      (node (ref "R22") (pin "2") (pinfunction "2_2") (pintype "passive"))
      (node (ref "R24") (pin "2") (pinfunction "2_2") (pintype "passive"))
      (node (ref "R26") (pin "2") (pinfunction "2_2") (pintype "passive"))
      (node (ref "R32") (pin "2") (pinfunction "2_2") (pintype "passive"))
      (node (ref "R34") (pin "2") (pinfunction "2_2") (pintype "passive"))
      (node (ref "R37") (pin "2") (pinfunction "2_2") (pintype "passive"))
      (node (ref "R4") (pin "2") (pinfunction "2_2") (pintype "passive"))
      (node (ref "R43") (pin "2") (pinfunction "2_2") (pintype "passive"))
      (node (ref "R48") (pin "2") (pinfunction "2_2") (pintype "passive"))
      (node (ref "R50") (pin "2") (pinfunction "2_2") (pintype "passive"))
      (node (ref "R52") (pin "2") (pinfunction "2_2") (pintype "passive"))
      (node (ref "R54") (pin "2") (pinfunction "2_2") (pintype "passive"))
      (node (ref "R6") (pin "2") (pinfunction "2_2") (pintype "passive"))
      (node (ref "R9") (pin "2") (pinfunction "2_2") (pintype "passive"))
      (node (ref "S1") (pin "1A") (pinfunction "P_1A") (pintype "passive"))
      (node (ref "S1") (pin "1B") (pinfunction "P1_1B") (pintype "passive"))
      (node (ref "TEENSY4.1") (pin "1") (pinfunction "GND_1") (pintype "power_in"))
      (node (ref "TEENSY4.1") (pin "34") (pinfunction "GND_34") (pintype "power_in"))
      (node (ref "TEENSY4.1") (pin "47") (pinfunction "GND_47") (pintype "power_in"))
      (node (ref "TEENSY4.1") (pin "56") (pinfunction "GND_56") (pintype "power_in"))
    )
    (net (code "17") (name "GPIO1_A") (class "Default")
      (node (ref "IC3") (pin "21") (pinfunction "GPIO1/INTA/DMIN_21") (pintype "bidirectional"))
      (node (ref "TEENSY4.1") (pin "21") (pinfunction "29/TX7_21") (pintype "bidirectional"))
    )
    (net (code "18") (name "GPIO1_B") (class "Default")
      (node (ref "IC8") (pin "21") (pinfunction "GPIO1/INTA/DMIN_21") (pintype "bidirectional"))
      (node (ref "TEENSY4.1") (pin "28") (pinfunction "36/CS_28") (pintype "bidirectional"))
    )
    (net (code "19") (name "GPIO2_A") (class "Default")
      (node (ref "IC3") (pin "20") (pinfunction "GPIO2/INTB/DMCLK_20") (pintype "bidirectional"))
      (node (ref "TEENSY4.1") (pin "20") (pinfunction "28/RX7_20") (pintype "bidirectional"))
    )
    (net (code "20") (name "GPIO2_B") (class "Default")
      (node (ref "IC8") (pin "20") (pinfunction "GPIO2/INTB/DMCLK_20") (pintype "bidirectional"))
      (node (ref "TEENSY4.1") (pin "27") (pinfunction "35/TX8_27") (pintype "bidirectional"))
    )
    (net (code "21") (name "LED") (class "Default")
      (node (ref "LED1") (pin "C") (pinfunction "C_C") (pintype "passive"))
      (node (ref "TEENSY4.1") (pin "23") (pinfunction "31_23") (pintype "bidirectional"))
    )
    (net (code "22") (name "LRCK") (class "Default")
      (node (ref "IC3") (pin "16") (pinfunction "LRCK_16") (pintype "bidirectional"))
      (node (ref "IC8") (pin "16") (pinfunction "LRCK_16") (pintype "bidirectional"))
      (node (ref "TEENSY4.1") (pin "42") (pinfunction "20/A6/TX5/LRCLK1_42") (pintype "bidirectional"))
    )
    (net (code "23") (name "Net-(C1-Pad2)") (class "Default")
      (node (ref "C1") (pin "2") (pinfunction "2_2") (pintype "passive"))
      (node (ref "R3") (pin "1") (pinfunction "1_1") (pintype "passive"))
    )
    (net (code "24") (name "Net-(C4-Pad2)") (class "Default")
      (node (ref "C4") (pin "2") (pinfunction "2_2") (pintype "passive"))
      (node (ref "R5") (pin "1") (pinfunction "1_1") (pintype "passive"))
    )
    (net (code "25") (name "Net-(C9-Pad2)") (class "Default")
      (node (ref "C9") (pin "2") (pinfunction "2_2") (pintype "passive"))
      (node (ref "R10") (pin "1") (pinfunction "1_1") (pintype "passive"))
    )
    (net (code "26") (name "Net-(C12-Pad2)") (class "Default")
      (node (ref "C12") (pin "2") (pinfunction "2_2") (pintype "passive"))
      (node (ref "R14") (pin "1") (pinfunction "1_1") (pintype "passive"))
    )
    (net (code "27") (name "Net-(C24-Pad2)") (class "Default")
      (node (ref "C24") (pin "2") (pinfunction "2_2") (pintype "passive"))
      (node (ref "R21") (pin "1") (pinfunction "1_1") (pintype "passive"))
    )
    (net (code "28") (name "Net-(C27-Pad2)") (class "Default")
      (node (ref "C27") (pin "2") (pinfunction "2_2") (pintype "passive"))
      (node (ref "R23") (pin "1") (pinfunction "1_1") (pintype "passive"))
    )
    (net (code "29") (name "Net-(C30-Pad2)") (class "Default")
      (node (ref "C30") (pin "2") (pinfunction "2_2") (pintype "passive"))
      (node (ref "R25") (pin "1") (pinfunction "1_1") (pintype "passive"))
    )
    (net (code "30") (name "Net-(C32-Pad2)") (class "Default")
      (node (ref "C32") (pin "2") (pinfunction "2_2") (pintype "passive"))
      (node (ref "R27") (pin "1") (pinfunction "1_1") (pintype "passive"))
    )
    (net (code "31") (name "Net-(C34-Pad2)") (class "Default")
      (node (ref "C34") (pin "2") (pinfunction "2_2") (pintype "passive"))
      (node (ref "R2") (pin "1") (pinfunction "1_1") (pintype "passive"))
    )
    (net (code "32") (name "Net-(C35-Pad2)") (class "Default")
      (node (ref "C35") (pin "2") (pinfunction "2_2") (pintype "passive"))
      (node (ref "R7") (pin "1") (pinfunction "1_1") (pintype "passive"))
    )
    (net (code "33") (name "Net-(C37-Pad2)") (class "Default")
      (node (ref "C37") (pin "2") (pinfunction "2_2") (pintype "passive"))
      (node (ref "R31") (pin "1") (pinfunction "1_1") (pintype "passive"))
    )
    (net (code "34") (name "Net-(C40-Pad2)") (class "Default")
      (node (ref "C40") (pin "2") (pinfunction "2_2") (pintype "passive"))
      (node (ref "R33") (pin "1") (pinfunction "1_1") (pintype "passive"))
    )
    (net (code "35") (name "Net-(C44-Pad2)") (class "Default")
      (node (ref "C44") (pin "2") (pinfunction "2_2") (pintype "passive"))
      (node (ref "R38") (pin "1") (pinfunction "1_1") (pintype "passive"))
    )
    (net (code "36") (name "Net-(C47-Pad2)") (class "Default")
      (node (ref "C47") (pin "2") (pinfunction "2_2") (pintype "passive"))
      (node (ref "R44") (pin "1") (pinfunction "1_1") (pintype "passive"))
    )
    (net (code "37") (name "Net-(C58-Pad2)") (class "Default")
      (node (ref "C58") (pin "2") (pinfunction "2_2") (pintype "passive"))
      (node (ref "R49") (pin "1") (pinfunction "1_1") (pintype "passive"))
    )
    (net (code "38") (name "Net-(C60-Pad2)") (class "Default")
      (node (ref "C60") (pin "2") (pinfunction "2_2") (pintype "passive"))
      (node (ref "R51") (pin "1") (pinfunction "1_1") (pintype "passive"))
    )
    (net (code "39") (name "Net-(C62-Pad2)") (class "Default")
      (node (ref "C62") (pin "2") (pinfunction "2_2") (pintype "passive"))
      (node (ref "R53") (pin "1") (pinfunction "1_1") (pintype "passive"))
    )
    (net (code "40") (name "Net-(C64-Pad2)") (class "Default")
      (node (ref "C64") (pin "2") (pinfunction "2_2") (pintype "passive"))
      (node (ref "R55") (pin "1") (pinfunction "1_1") (pintype "passive"))
    )
    (net (code "41") (name "Net-(C65-Pad2)") (class "Default")
      (node (ref "C65") (pin "2") (pinfunction "2_2") (pintype "passive"))
      (node (ref "R12") (pin "1") (pinfunction "1_1") (pintype "passive"))
    )
    (net (code "42") (name "Net-(C66-Pad2)") (class "Default")
      (node (ref "C66") (pin "2") (pinfunction "2_2") (pintype "passive"))
      (node (ref "R16") (pin "1") (pinfunction "1_1") (pintype "passive"))
    )
    (net (code "43") (name "Net-(C67-Pad2)") (class "Default")
      (node (ref "C67") (pin "2") (pinfunction "2_2") (pintype "passive"))
      (node (ref "R30") (pin "1") (pinfunction "1_1") (pintype "passive"))
    )
    (net (code "44") (name "Net-(C68-Pad2)") (class "Default")
      (node (ref "C68") (pin "2") (pinfunction "2_2") (pintype "passive"))
      (node (ref "R35") (pin "1") (pinfunction "1_1") (pintype "passive"))
    )
    (net (code "45") (name "Net-(C69-Pad2)") (class "Default")
      (node (ref "C69") (pin "2") (pinfunction "2_2") (pintype "passive"))
      (node (ref "R41") (pin "1") (pinfunction "1_1") (pintype "passive"))
    )
    (net (code "46") (name "Net-(C70-Pad2)") (class "Default")
      (node (ref "C70") (pin "2") (pinfunction "2_2") (pintype "passive"))
      (node (ref "R45") (pin "1") (pinfunction "1_1") (pintype "passive"))
    )
    (net (code "47") (name "Net-(CAN_DOWNA-K)") (class "Default")
      (node (ref "C17") (pin "1") (pinfunction "1_1") (pintype "passive"))
      (node (ref "CAN_DOWN") (pin "1") (pinfunction "K_1") (pintype "passive"))
      (node (ref "CAN_UP") (pin "1") (pinfunction "K_1") (pintype "passive"))
      (node (ref "D1") (pin "C") (pinfunction "C_C") (pintype "passive"))
      (node (ref "L1") (pin "2") (pinfunction "2_2") (pintype "passive"))
    )
    (net (code "48") (name "Net-(IC1A-+IN)") (class "Default")
      (node (ref "C18") (pin "2") (pinfunction "2_2") (pintype "passive"))
      (node (ref "C3") (pin "2") (pinfunction "2_2") (pintype "passive"))
      (node (ref "C8") (pin "1") (pinfunction "1_1") (pintype "passive"))
      (node (ref "IC1") (pin "3") (pinfunction "+IN_3") (pintype "input"))
      (node (ref "IC1") (pin "5") (pinfunction "+IN_5") (pintype "input"))
      (node (ref "IC2") (pin "3") (pinfunction "+IN_3") (pintype "input"))
      (node (ref "IC2") (pin "5") (pinfunction "+IN_5") (pintype "input"))
      (node (ref "R13") (pin "2") (pinfunction "2_2") (pintype "passive"))
    )
    (net (code "49") (name "Net-(IC1A--IN)") (class "Default")
      (node (ref "IC1") (pin "2") (pinfunction "-IN_2") (pintype "input"))
      (node (ref "R1") (pin "1") (pinfunction "1_1") (pintype "passive"))
      (node (ref "R3") (pin "2") (pinfunction "2_2") (pintype "passive"))
    )
    (net (code "50") (name "Net-(IC1A-OUT)") (class "Default")
      (node (ref "C34") (pin "1") (pinfunction "1_1") (pintype "passive"))
      (node (ref "IC1") (pin "1") (pinfunction "OUT_1") (pintype "output"))
      (node (ref "R1") (pin "2") (pinfunction "2_2") (pintype "passive"))
    )
    (net (code "51") (name "Net-(IC1B--IN)") (class "Default")
      (node (ref "IC1") (pin "6") (pinfunction "-IN_6") (pintype "input"))
      (node (ref "R5") (pin "2") (pinfunction "2_2") (pintype "passive"))
      (node (ref "R8") (pin "1") (pinfunction "1_1") (pintype "passive"))
    )
    (net (code "52") (name "Net-(IC1B-OUT)") (class "Default")
      (node (ref "C35") (pin "1") (pinfunction "1_1") (pintype "passive"))
      (node (ref "IC1") (pin "7") (pinfunction "OUT_7") (pintype "output"))
      (node (ref "R8") (pin "2") (pinfunction "2_2") (pintype "passive"))
    )
    (net (code "53") (name "Net-(IC2A--IN)") (class "Default")
      (node (ref "IC2") (pin "2") (pinfunction "-IN_2") (pintype "input"))
      (node (ref "R10") (pin "2") (pinfunction "2_2") (pintype "passive"))
      (node (ref "R11") (pin "1") (pinfunction "1_1") (pintype "passive"))
    )
    (net (code "54") (name "Net-(IC2A-OUT)") (class "Default")
      (node (ref "C65") (pin "1") (pinfunction "1_1") (pintype "passive"))
      (node (ref "IC2") (pin "1") (pinfunction "OUT_1") (pintype "output"))
      (node (ref "R11") (pin "2") (pinfunction "2_2") (pintype "passive"))
    )
    (net (code "55") (name "Net-(IC2B--IN)") (class "Default")
      (node (ref "IC2") (pin "6") (pinfunction "-IN_6") (pintype "input"))
      (node (ref "R14") (pin "2") (pinfunction "2_2") (pintype "passive"))
      (node (ref "R17") (pin "1") (pinfunction "1_1") (pintype "passive"))
    )
    (net (code "56") (name "Net-(IC2B-OUT)") (class "Default")
      (node (ref "C66") (pin "1") (pinfunction "1_1") (pintype "passive"))
      (node (ref "IC2") (pin "7") (pinfunction "OUT_7") (pintype "output"))
      (node (ref "R17") (pin "2") (pinfunction "2_2") (pintype "passive"))
    )
    (net (code "57") (name "Net-(IC3-LDO)") (class "Default")
      (node (ref "C15") (pin "1") (pinfunction "1_1") (pintype "passive"))
      (node (ref "C16") (pin "1") (pinfunction "1_1") (pintype "passive"))
      (node (ref "IC3") (pin "11") (pinfunction "LDO_11") (pintype "bidirectional"))
    )
    (net (code "58") (name "Net-(IC3-VINL1{slash}VIN1P)") (class "Default")
      (node (ref "C5") (pin "1") (pinfunction "1_1") (pintype "passive"))
      (node (ref "IC3") (pin "3") (pinfunction "VINL1/VIN1P_3") (pintype "input"))
      (node (ref "R7") (pin "2") (pinfunction "2_2") (pintype "passive"))
    )
    (net (code "59") (name "Net-(IC3-VINL2{slash}VIN1M)") (class "Default")
      (node (ref "C21") (pin "1") (pinfunction "1_1") (pintype "passive"))
      (node (ref "IC3") (pin "1") (pinfunction "VINL2/VIN1M_1") (pintype "input"))
      (node (ref "R16") (pin "2") (pinfunction "2_2") (pintype "passive"))
    )
    (net (code "60") (name "Net-(IC3-VINL3{slash}VIN4P)") (class "Default")
      (node (ref "C26") (pin "1") (pinfunction "1_1") (pintype "passive"))
      (node (ref "IC3") (pin "29") (pinfunction "VINL3/VIN4P_29") (pintype "input"))
      (node (ref "R23") (pin "2") (pinfunction "2_2") (pintype "passive"))
    )
    (net (code "61") (name "Net-(IC3-VINL4{slash}VIN4M)") (class "Default")
      (node (ref "C31") (pin "1") (pinfunction "1_1") (pintype "passive"))
      (node (ref "IC3") (pin "27") (pinfunction "VINL4/VIN4M_27") (pintype "input"))
      (node (ref "R27") (pin "2") (pinfunction "2_2") (pintype "passive"))
    )
    (net (code "62") (name "Net-(IC3-VINR1{slash}VIN2P)") (class "Default")
      (node (ref "C2") (pin "1") (pinfunction "1_1") (pintype "passive"))
      (node (ref "IC3") (pin "4") (pinfunction "VINR1/VIN2P_4") (pintype "input"))
      (node (ref "R2") (pin "2") (pinfunction "2_2") (pintype "passive"))
    )
    (net (code "63") (name "Net-(IC3-VINR2{slash}VIN2M)") (class "Default")
      (node (ref "C11") (pin "1") (pinfunction "1_1") (pintype "passive"))
      (node (ref "IC3") (pin "2") (pinfunction "VINR2/VIN2M_2") (pintype "input"))
      (node (ref "R12") (pin "2") (pinfunction "2_2") (pintype "passive"))
    )
    (net (code "64") (name "Net-(IC3-VINR3{slash}VIN3P)") (class "Default")
      (node (ref "C23") (pin "1") (pinfunction "1_1") (pintype "passive"))
      (node (ref "IC3") (pin "30") (pinfunction "VINR3/VIN3P_30") (pintype "input"))
      (node (ref "R21") (pin "2") (pinfunction "2_2") (pintype "passive"))
    )
    (net (code "65") (name "Net-(IC3-VINR4{slash}VIN3M)") (class "Default")
      (node (ref "C28") (pin "1") (pinfunction "1_1") (pintype "passive"))
      (node (ref "IC3") (pin "28") (pinfunction "VINR4/VIN3M_28") (pintype "input"))
      (node (ref "R25") (pin "2") (pinfunction "2_2") (pintype "passive"))
    )
    (net (code "66") (name "Net-(IC3-VREF)") (class "Default")
      (node (ref "C13") (pin "1") (pinfunction "1_1") (pintype "passive"))
      (node (ref "IC3") (pin "6") (pinfunction "VREF_6") (pintype "output"))
      (node (ref "R13") (pin "1") (pinfunction "1_1") (pintype "passive"))
    )
    (net (code "67") (name "Net-(IC6A-+IN)") (class "Default")
      (node (ref "C39") (pin "2") (pinfunction "2_2") (pintype "passive"))
      (node (ref "C43") (pin "1") (pinfunction "1_1") (pintype "passive"))
      (node (ref "C52") (pin "2") (pinfunction "2_2") (pintype "passive"))
      (node (ref "IC6") (pin "3") (pinfunction "+IN_3") (pintype "input"))
      (node (ref "IC6") (pin "5") (pinfunction "+IN_5") (pintype "input"))
      (node (ref "IC7") (pin "3") (pinfunction "+IN_3") (pintype "input"))
      (node (ref "IC7") (pin "5") (pinfunction "+IN_5") (pintype "input"))
      (node (ref "R40") (pin "2") (pinfunction "2_2") (pintype "passive"))
    )
    (net (code "68") (name "Net-(IC6A--IN)") (class "Default")
      (node (ref "IC6") (pin "2") (pinfunction "-IN_2") (pintype "input"))
      (node (ref "R29") (pin "1") (pinfunction "1_1") (pintype "passive"))
      (node (ref "R31") (pin "2") (pinfunction "2_2") (pintype "passive"))
    )
    (net (code "69") (name "Net-(IC6A-OUT)") (class "Default")
      (node (ref "C67") (pin "1") (pinfunction "1_1") (pintype "passive"))
      (node (ref "IC6") (pin "1") (pinfunction "OUT_1") (pintype "output"))
      (node (ref "R29") (pin "2") (pinfunction "2_2") (pintype "passive"))
    )
    (net (code "70") (name "Net-(IC6B--IN)") (class "Default")
      (node (ref "IC6") (pin "6") (pinfunction "-IN_6") (pintype "input"))
      (node (ref "R33") (pin "2") (pinfunction "2_2") (pintype "passive"))
      (node (ref "R36") (pin "1") (pinfunction "1_1") (pintype "passive"))
    )
    (net (code "71") (name "Net-(IC6B-OUT)") (class "Default")
      (node (ref "C68") (pin "1") (pinfunction "1_1") (pintype "passive"))
      (node (ref "IC6") (pin "7") (pinfunction "OUT_7") (pintype "output"))
      (node (ref "R36") (pin "2") (pinfunction "2_2") (pintype "passive"))
    )
    (net (code "72") (name "Net-(IC7A--IN)") (class "Default")
      (node (ref "IC7") (pin "2") (pinfunction "-IN_2") (pintype "input"))
      (node (ref "R38") (pin "2") (pinfunction "2_2") (pintype "passive"))
      (node (ref "R39") (pin "1") (pinfunction "1_1") (pintype "passive"))
    )
    (net (code "73") (name "Net-(IC7A-OUT)") (class "Default")
      (node (ref "C69") (pin "1") (pinfunction "1_1") (pintype "passive"))
      (node (ref "IC7") (pin "1") (pinfunction "OUT_1") (pintype "output"))
      (node (ref "R39") (pin "2") (pinfunction "2_2") (pintype "passive"))
    )
    (net (code "74") (name "Net-(IC7B--IN)") (class "Default")
      (node (ref "IC7") (pin "6") (pinfunction "-IN_6") (pintype "input"))
      (node (ref "R44") (pin "2") (pinfunction "2_2") (pintype "passive"))
      (node (ref "R46") (pin "1") (pinfunction "1_1") (pintype "passive"))
    )
    (net (code "75") (name "Net-(IC7B-OUT)") (class "Default")
      (node (ref "C70") (pin "1") (pinfunction "1_1") (pintype "passive"))
      (node (ref "IC7") (pin "7") (pinfunction "OUT_7") (pintype "output"))
      (node (ref "R46") (pin "2") (pinfunction "2_2") (pintype "passive"))
    )
    (net (code "76") (name "Net-(IC8-LDO)") (class "Default")
      (node (ref "C50") (pin "1") (pinfunction "1_1") (pintype "passive"))
      (node (ref "C51") (pin "1") (pinfunction "1_1") (pintype "passive"))
      (node (ref "IC8") (pin "11") (pinfunction "LDO_11") (pintype "bidirectional"))
    )
    (net (code "77") (name "Net-(IC8-VINL1{slash}VIN1P)") (class "Default")
      (node (ref "C41") (pin "1") (pinfunction "1_1") (pintype "passive"))
      (node (ref "IC8") (pin "3") (pinfunction "VINL1/VIN1P_3") (pintype "input"))
      (node (ref "R35") (pin "2") (pinfunction "2_2") (pintype "passive"))
    )
    (net (code "78") (name "Net-(IC8-VINL2{slash}VIN1M)") (class "Default")
      (node (ref "C55") (pin "1") (pinfunction "1_1") (pintype "passive"))
      (node (ref "IC8") (pin "1") (pinfunction "VINL2/VIN1M_1") (pintype "input"))
      (node (ref "R45") (pin "2") (pinfunction "2_2") (pintype "passive"))
    )
    (net (code "79") (name "Net-(IC8-VINL3{slash}VIN4P)") (class "Default")
      (node (ref "C59") (pin "1") (pinfunction "1_1") (pintype "passive"))
      (node (ref "IC8") (pin "29") (pinfunction "VINL3/VIN4P_29") (pintype "input"))
      (node (ref "R51") (pin "2") (pinfunction "2_2") (pintype "passive"))
    )
    (net (code "80") (name "Net-(IC8-VINL4{slash}VIN4M)") (class "Default")
      (node (ref "C63") (pin "1") (pinfunction "1_1") (pintype "passive"))
      (node (ref "IC8") (pin "27") (pinfunction "VINL4/VIN4M_27") (pintype "input"))
      (node (ref "R55") (pin "2") (pinfunction "2_2") (pintype "passive"))
    )
    (net (code "81") (name "Net-(IC8-VINR1{slash}VIN2P)") (class "Default")
      (node (ref "C38") (pin "1") (pinfunction "1_1") (pintype "passive"))
      (node (ref "IC8") (pin "4") (pinfunction "VINR1/VIN2P_4") (pintype "input"))
      (node (ref "R30") (pin "2") (pinfunction "2_2") (pintype "passive"))
    )
    (net (code "82") (name "Net-(IC8-VINR2{slash}VIN2M)") (class "Default")
      (node (ref "C46") (pin "1") (pinfunction "1_1") (pintype "passive"))
      (node (ref "IC8") (pin "2") (pinfunction "VINR2/VIN2M_2") (pintype "input"))
      (node (ref "R41") (pin "2") (pinfunction "2_2") (pintype "passive"))
    )
    (net (code "83") (name "Net-(IC8-VINR3{slash}VIN3P)") (class "Default")
      (node (ref "C57") (pin "1") (pinfunction "1_1") (pintype "passive"))
      (node (ref "IC8") (pin "30") (pinfunction "VINR3/VIN3P_30") (pintype "input"))
      (node (ref "R49") (pin "2") (pinfunction "2_2") (pintype "passive"))
    )
    (net (code "84") (name "Net-(IC8-VINR4{slash}VIN3M)") (class "Default")
      (node (ref "C61") (pin "1") (pinfunction "1_1") (pintype "passive"))
      (node (ref "IC8") (pin "28") (pinfunction "VINR4/VIN3M_28") (pintype "input"))
      (node (ref "R53") (pin "2") (pinfunction "2_2") (pintype "passive"))
    )
    (net (code "85") (name "Net-(IC8-VREF)") (class "Default")
      (node (ref "C48") (pin "1") (pinfunction "1_1") (pintype "passive"))
      (node (ref "IC8") (pin "6") (pinfunction "VREF_6") (pintype "output"))
      (node (ref "R40") (pin "1") (pinfunction "1_1") (pintype "passive"))
    )
    (net (code "86") (name "Net-(IN1AA-K)") (class "Default")
      (node (ref "C1") (pin "1") (pinfunction "1_1") (pintype "passive"))
      (node (ref "IN1A") (pin "1") (pinfunction "K_1") (pintype "passive"))
      (node (ref "R4") (pin "1") (pinfunction "1_1") (pintype "passive"))
    )
    (net (code "87") (name "Net-(IN1AB-K)") (class "Default")
      (node (ref "C4") (pin "1") (pinfunction "1_1") (pintype "passive"))
      (node (ref "IN1A") (pin "2") (pinfunction "K_2") (pintype "passive"))
      (node (ref "R6") (pin "1") (pinfunction "1_1") (pintype "passive"))
    )
    (net (code "88") (name "Net-(IN1AC-K)") (class "Default")
      (node (ref "C9") (pin "1") (pinfunction "1_1") (pintype "passive"))
      (node (ref "IN1A") (pin "3") (pinfunction "K_3") (pintype "passive"))
      (node (ref "R9") (pin "1") (pinfunction "1_1") (pintype "passive"))
    )
    (net (code "89") (name "Net-(IN1AD-K)") (class "Default")
      (node (ref "C12") (pin "1") (pinfunction "1_1") (pintype "passive"))
      (node (ref "IN1A") (pin "4") (pinfunction "K_4") (pintype "passive"))
      (node (ref "R15") (pin "1") (pinfunction "1_1") (pintype "passive"))
    )
    (net (code "90") (name "Net-(IN1BA-K)") (class "Default")
      (node (ref "C24") (pin "1") (pinfunction "1_1") (pintype "passive"))
      (node (ref "IN1B") (pin "1") (pinfunction "K_1") (pintype "passive"))
      (node (ref "R20") (pin "1") (pinfunction "1_1") (pintype "passive"))
    )
    (net (code "91") (name "Net-(IN1BB-K)") (class "Default")
      (node (ref "C27") (pin "1") (pinfunction "1_1") (pintype "passive"))
      (node (ref "IN1B") (pin "2") (pinfunction "K_2") (pintype "passive"))
      (node (ref "R22") (pin "1") (pinfunction "1_1") (pintype "passive"))
    )
    (net (code "92") (name "Net-(IN1BC-K)") (class "Default")
      (node (ref "C30") (pin "1") (pinfunction "1_1") (pintype "passive"))
      (node (ref "IN1B") (pin "3") (pinfunction "K_3") (pintype "passive"))
      (node (ref "R24") (pin "1") (pinfunction "1_1") (pintype "passive"))
    )
    (net (code "93") (name "Net-(IN1BD-K)") (class "Default")
      (node (ref "C32") (pin "1") (pinfunction "1_1") (pintype "passive"))
      (node (ref "IN1B") (pin "4") (pinfunction "K_4") (pintype "passive"))
      (node (ref "R26") (pin "1") (pinfunction "1_1") (pintype "passive"))
    )
    (net (code "94") (name "Net-(IN2AA-K)") (class "Default")
      (node (ref "C37") (pin "1") (pinfunction "1_1") (pintype "passive"))
      (node (ref "IN2A") (pin "1") (pinfunction "K_1") (pintype "passive"))
      (node (ref "R32") (pin "1") (pinfunction "1_1") (pintype "passive"))
    )
    (net (code "95") (name "Net-(IN2AB-K)") (class "Default")
      (node (ref "C40") (pin "1") (pinfunction "1_1") (pintype "passive"))
      (node (ref "IN2A") (pin "2") (pinfunction "K_2") (pintype "passive"))
      (node (ref "R34") (pin "1") (pinfunction "1_1") (pintype "passive"))
    )
    (net (code "96") (name "Net-(IN2AC-K)") (class "Default")
      (node (ref "C44") (pin "1") (pinfunction "1_1") (pintype "passive"))
      (node (ref "IN2A") (pin "3") (pinfunction "K_3") (pintype "passive"))
      (node (ref "R37") (pin "1") (pinfunction "1_1") (pintype "passive"))
    )
    (net (code "97") (name "Net-(IN2AD-K)") (class "Default")
      (node (ref "C47") (pin "1") (pinfunction "1_1") (pintype "passive"))
      (node (ref "IN2A") (pin "4") (pinfunction "K_4") (pintype "passive"))
      (node (ref "R43") (pin "1") (pinfunction "1_1") (pintype "passive"))
    )
    (net (code "98") (name "Net-(IN2BA-K)") (class "Default")
      (node (ref "C58") (pin "1") (pinfunction "1_1") (pintype "passive"))
      (node (ref "IN2B") (pin "1") (pinfunction "K_1") (pintype "passive"))
      (node (ref "R48") (pin "1") (pinfunction "1_1") (pintype "passive"))
    )
    (net (code "99") (name "Net-(IN2BB-K)") (class "Default")
      (node (ref "C60") (pin "1") (pinfunction "1_1") (pintype "passive"))
      (node (ref "IN2B") (pin "2") (pinfunction "K_2") (pintype "passive"))
      (node (ref "R50") (pin "1") (pinfunction "1_1") (pintype "passive"))
    )
    (net (code "100") (name "Net-(IN2BC-K)") (class "Default")
      (node (ref "C62") (pin "1") (pinfunction "1_1") (pintype "passive"))
      (node (ref "IN2B") (pin "3") (pinfunction "K_3") (pintype "passive"))
      (node (ref "R52") (pin "1") (pinfunction "1_1") (pintype "passive"))
    )
    (net (code "101") (name "Net-(IN2BD-K)") (class "Default")
      (node (ref "C64") (pin "1") (pinfunction "1_1") (pintype "passive"))
      (node (ref "IN2B") (pin "4") (pinfunction "K_4") (pintype "passive"))
      (node (ref "R54") (pin "1") (pinfunction "1_1") (pintype "passive"))
    )
    (net (code "102") (name "Net-(LED1-PadA)") (class "Default")
      (node (ref "LED1") (pin "A") (pinfunction "A_A") (pintype "passive"))
      (node (ref "R56") (pin "1") (pinfunction "1_1") (pintype "passive"))
    )
    (net (code "103") (name "Net-(TEENSY4.1A-9{slash}OUT1C)") (class "Default")
      (node (ref "JP1") (pin "1") (pinfunction "1_1") (pintype "passive"))
      (node (ref "TEENSY4.1") (pin "11") (pinfunction "9/OUT1C_11") (pintype "bidirectional"))
    )
    (net (code "104") (name "SCL") (class "Default")
      (node (ref "IC3") (pin "24") (pinfunction "MC/SCL_24") (pintype "input"))
      (node (ref "IC8") (pin "24") (pinfunction "MC/SCL_24") (pintype "input"))
      (node (ref "R19") (pin "1") (pinfunction "1_1") (pintype "passive"))
      (node (ref "TEENSY4.1") (pin "41") (pinfunction "19/A5/SCL_41") (pintype "bidirectional"))
    )
    (net (code "105") (name "SDA") (class "Default")
      (node (ref "IC3") (pin "23") (pinfunction "MOSI/SDA_23") (pintype "bidirectional"))
      (node (ref "IC8") (pin "23") (pinfunction "MOSI/SDA_23") (pintype "bidirectional"))
      (node (ref "R18") (pin "1") (pinfunction "1_1") (pintype "passive"))
      (node (ref "TEENSY4.1") (pin "40") (pinfunction "18/A4/SDA_40") (pintype "bidirectional"))
    )
    (net (code "106") (name "VBAT") (class "Default")
      (node (ref "TEENSY4.1") (pin "54") (pinfunction "VBAT_54") (pintype "power_in"))
    )
    (net (code "107") (name "VDD") (class "Default")
      (node (ref "C19") (pin "1") (pinfunction "1_1") (pintype "passive"))
      (node (ref "C20") (pin "1") (pinfunction "1_1") (pintype "passive"))
      (node (ref "C25") (pin "1") (pinfunction "1_1") (pintype "passive"))
      (node (ref "C29") (pin "1") (pinfunction "1_1") (pintype "passive"))
      (node (ref "C53") (pin "1") (pinfunction "1_1") (pintype "passive"))
      (node (ref "C54") (pin "1") (pinfunction "1_1") (pintype "passive"))
      (node (ref "IC3") (pin "13") (pinfunction "DVDD_13") (pintype "power_in"))
      (node (ref "IC3") (pin "14") (pinfunction "IOVDD_14") (pintype "power_in"))
      (node (ref "IC4") (pin "3") (pinfunction "VCC_3") (pintype "power_in"))
      (node (ref "IC8") (pin "13") (pinfunction "DVDD_13") (pintype "power_in"))
      (node (ref "IC8") (pin "14") (pinfunction "IOVDD_14") (pintype "power_in"))
      (node (ref "IC8") (pin "25") (pinfunction "MS/AD_25") (pintype "input"))
      (node (ref "R18") (pin "2") (pinfunction "2_2") (pintype "passive"))
      (node (ref "R19") (pin "2") (pinfunction "2_2") (pintype "passive"))
      (node (ref "R47") (pin "2") (pinfunction "2_2") (pintype "passive"))
      (node (ref "R56") (pin "2") (pinfunction "2_2") (pintype "passive"))
      (node (ref "TEENSY4.1") (pin "15") (pinfunction "3.3V_15") (pintype "output"))
      (node (ref "TEENSY4.1") (pin "46") (pinfunction "3.3V_46") (pintype "output"))
      (node (ref "TEENSY4.1") (pin "55") (pinfunction "3.3V_55") (pintype "output"))
    )
    (net (code "108") (name "VDDA") (class "Default")
      (node (ref "C10") (pin "1") (pinfunction "1_1") (pintype "passive"))
      (node (ref "C14") (pin "1") (pinfunction "1_1") (pintype "passive"))
      (node (ref "C22") (pin "1") (pinfunction "1_1") (pintype "passive"))
      (node (ref "C36") (pin "1") (pinfunction "1_1") (pintype "passive"))
      (node (ref "C42") (pin "1") (pinfunction "1_1") (pintype "passive"))
      (node (ref "C45") (pin "1") (pinfunction "1_1") (pintype "passive"))
      (node (ref "C49") (pin "1") (pinfunction "1_1") (pintype "passive"))
      (node (ref "C56") (pin "1") (pinfunction "1_1") (pintype "passive"))
      (node (ref "C7") (pin "1") (pinfunction "1_1") (pintype "passive"))
      (node (ref "IC1") (pin "8") (pinfunction "V+_8") (pintype "power_in"))
      (node (ref "IC2") (pin "8") (pinfunction "V+_8") (pintype "power_in"))
      (node (ref "IC3") (pin "8") (pinfunction "AVDD_8") (pintype "power_in"))
      (node (ref "IC5") (pin "5") (pinfunction "OUT_5") (pintype "output"))
      (node (ref "IC6") (pin "8") (pinfunction "V+_8") (pintype "power_in"))
      (node (ref "IC7") (pin "8") (pinfunction "V+_8") (pintype "power_in"))
      (node (ref "IC8") (pin "8") (pinfunction "AVDD_8") (pintype "power_in"))
    )
    (net (code "109") (name "unconnected-(DN1-C4-Pad4)") (class "Default")
      (node (ref "DN1") (pin "4") (pinfunction "C4_4") (pintype "passive"))
    )
    (net (code "110") (name "unconnected-(IC3-GPIO3{slash}INTC-Pad19)") (class "Default")
      (node (ref "IC3") (pin "19") (pinfunction "GPIO3/INTC_19") (pintype "bidirectional"))
    )
    (net (code "111") (name "unconnected-(IC3-MICBIAS-Pad5)") (class "Default")
      (node (ref "IC3") (pin "5") (pinfunction "MICBIAS_5") (pintype "input"))
    )
    (net (code "112") (name "unconnected-(IC3-SCKI-Pad15)") (class "Default")
      (node (ref "IC3") (pin "15") (pinfunction "SCKI_15") (pintype "input"))
    )
    (net (code "113") (name "unconnected-(IC3-XI-Pad10)") (class "Default")
      (node (ref "IC3") (pin "10") (pinfunction "XI_10") (pintype "input"))
    )
    (net (code "114") (name "unconnected-(IC3-XO-Pad9)") (class "Default")
      (node (ref "IC3") (pin "9") (pinfunction "XO_9") (pintype "output"))
    )
    (net (code "115") (name "unconnected-(IC4-S-Pad8)") (class "Default")
      (node (ref "IC4") (pin "8") (pinfunction "S_8") (pintype "input"))
    )
    (net (code "116") (name "unconnected-(IC4-SHDN-Pad5)") (class "Default")
      (node (ref "IC4") (pin "5") (pinfunction "SHDN_5") (pintype "input"))
    )
    (net (code "117") (name "unconnected-(IC8-GPIO3{slash}INTC-Pad19)") (class "Default")
      (node (ref "IC8") (pin "19") (pinfunction "GPIO3/INTC_19") (pintype "bidirectional"))
    )
    (net (code "118") (name "unconnected-(IC8-MICBIAS-Pad5)") (class "Default")
      (node (ref "IC8") (pin "5") (pinfunction "MICBIAS_5") (pintype "input"))
    )
    (net (code "119") (name "unconnected-(IC8-SCKI-Pad15)") (class "Default")
      (node (ref "IC8") (pin "15") (pinfunction "SCKI_15") (pintype "input"))
    )
    (net (code "120") (name "unconnected-(IC8-XI-Pad10)") (class "Default")
      (node (ref "IC8") (pin "10") (pinfunction "XI_10") (pintype "input"))
    )
    (net (code "121") (name "unconnected-(IC8-XO-Pad9)") (class "Default")
      (node (ref "IC8") (pin "9") (pinfunction "XO_9") (pintype "output"))
    )
    (net (code "122") (name "unconnected-(TEENSY4.1A-2{slash}OUT2-Pad4)") (class "Default")
      (node (ref "TEENSY4.1") (pin "4") (pinfunction "2/OUT2_4") (pintype "bidirectional"))
    )
    (net (code "123") (name "unconnected-(TEENSY4.1A-3{slash}LRCLK2-Pad5)") (class "Default")
      (node (ref "TEENSY4.1") (pin "5") (pinfunction "3/LRCLK2_5") (pintype "bidirectional"))
    )
    (net (code "124") (name "unconnected-(TEENSY4.1A-4{slash}BCLK2-Pad6)") (class "Default")
      (node (ref "TEENSY4.1") (pin "6") (pinfunction "4/BCLK2_6") (pintype "bidirectional"))
    )
    (net (code "125") (name "unconnected-(TEENSY4.1A-5{slash}IN2-Pad7)") (class "Default")
      (node (ref "TEENSY4.1") (pin "7") (pinfunction "5/IN2_7") (pintype "bidirectional"))
    )
    (net (code "126") (name "unconnected-(TEENSY4.1A-7{slash}RX2{slash}OUT1A-Pad9)") (class "Default")
      (node (ref "TEENSY4.1") (pin "9") (pinfunction "7/RX2/OUT1A_9") (pintype "bidirectional"))
    )
    (net (code "127") (name "unconnected-(TEENSY4.1A-10{slash}CS{slash}MOSR-Pad12)") (class "Default")
      (node (ref "TEENSY4.1") (pin "12") (pinfunction "10/CS/MOSR_12") (pintype "bidirectional"))
    )
    (net (code "128") (name "unconnected-(TEENSY4.1A-11{slash}MOSI-Pad13)") (class "Default")
      (node (ref "TEENSY4.1") (pin "13") (pinfunction "11/MOSI_13") (pintype "bidirectional"))
    )
    (net (code "129") (name "unconnected-(TEENSY4.1A-12{slash}MISO{slash}MQSL-Pad14)") (class "Default")
      (node (ref "TEENSY4.1") (pin "14") (pinfunction "12/MISO/MQSL_14") (pintype "bidirectional"))
    )
    (net (code "130") (name "unconnected-(TEENSY4.1A-13(LED){slash}SCK-Pad35)") (class "Default")
      (node (ref "TEENSY4.1") (pin "35") (pinfunction "13(LED)/SCK_35") (pintype "bidirectional"))
    )
    (net (code "131") (name "unconnected-(TEENSY4.1A-14{slash}A0{slash}TX3{slash}SPDIFOUT-Pad36)") (class "Default")
      (node (ref "TEENSY4.1") (pin "36") (pinfunction "14/A0/TX3/SPDIFOUT_36") (pintype "bidirectional"))
    )
    (net (code "132") (name "unconnected-(TEENSY4.1A-15{slash}A1{slash}RX3{slash}SPDIFIN-Pad37)") (class "Default")
      (node (ref "TEENSY4.1") (pin "37") (pinfunction "15/A1/RX3/SPDIFIN_37") (pintype "bidirectional"))
    )
    (net (code "133") (name "unconnected-(TEENSY4.1A-16{slash}A2{slash}RX4{slash}SCL1-Pad38)") (class "Default")
      (node (ref "TEENSY4.1") (pin "38") (pinfunction "16/A2/RX4/SCL1_38") (pintype "bidirectional"))
    )
    (net (code "134") (name "unconnected-(TEENSY4.1A-17{slash}A3{slash}TX4{slash}SDA1-Pad39)") (class "Default")
      (node (ref "TEENSY4.1") (pin "39") (pinfunction "17/A3/TX4/SDA1_39") (pintype "bidirectional"))
    )
    (net (code "135") (name "unconnected-(TEENSY4.1A-22{slash}A8-Pad44)") (class "Default")
      (node (ref "TEENSY4.1") (pin "44") (pinfunction "22/A8_44") (pintype "bidirectional"))
    )
    (net (code "136") (name "unconnected-(TEENSY4.1A-23{slash}A9{slash}MCLK1-Pad45)") (class "Default")
      (node (ref "TEENSY4.1") (pin "45") (pinfunction "23/A9/MCLK1_45") (pintype "bidirectional"))
    )
    (net (code "137") (name "unconnected-(TEENSY4.1A-26{slash}A12{slash}MOSI1-Pad18)") (class "Default")
      (node (ref "TEENSY4.1") (pin "18") (pinfunction "26/A12/MOSI1_18") (pintype "bidirectional"))
    )
    (net (code "138") (name "unconnected-(TEENSY4.1A-27A13{slash}{slash}SCK1-Pad19)") (class "Default")
      (node (ref "TEENSY4.1") (pin "19") (pinfunction "27A13//SCK1_19") (pintype "bidirectional"))
    )
    (net (code "139") (name "unconnected-(TEENSY4.1A-33{slash}MCLK2-Pad25)") (class "Default")
      (node (ref "TEENSY4.1") (pin "25") (pinfunction "33/MCLK2_25") (pintype "bidirectional"))
    )
    (net (code "140") (name "unconnected-(TEENSY4.1A-34{slash}RX8-Pad26)") (class "Default")
      (node (ref "TEENSY4.1") (pin "26") (pinfunction "34/RX8_26") (pintype "bidirectional"))
    )
    (net (code "141") (name "unconnected-(TEENSY4.1A-37{slash}CS-Pad29)") (class "Default")
      (node (ref "TEENSY4.1") (pin "29") (pinfunction "37/CS_29") (pintype "bidirectional"))
    )
    (net (code "142") (name "unconnected-(TEENSY4.1A-38{slash}A15{slash}CS1{slash}IN1-Pad30)") (class "Default")
      (node (ref "TEENSY4.1") (pin "30") (pinfunction "38/A15/CS1/IN1_30") (pintype "bidirectional"))
    )
    (net (code "143") (name "unconnected-(TEENSY4.1A-39{slash}A15{slash}MISO1{slash}OUT1A-Pad31)") (class "Default")
      (node (ref "TEENSY4.1") (pin "31") (pinfunction "39/A15/MISO1/OUT1A_31") (pintype "bidirectional"))
    )
    (net (code "144") (name "unconnected-(TEENSY4.1A-40{slash}A16-Pad32)") (class "Default")
      (node (ref "TEENSY4.1") (pin "32") (pinfunction "40/A16_32") (pintype "bidirectional"))
    )
    (net (code "145") (name "unconnected-(TEENSY4.1A-41{slash}A17-Pad33)") (class "Default")
      (node (ref "TEENSY4.1") (pin "33") (pinfunction "41/A17_33") (pintype "bidirectional"))
    )
    (net (code "146") (name "unconnected-(TEENSY4.1A-PROGRAM-Pad57)") (class "Default")
      (node (ref "TEENSY4.1") (pin "57") (pinfunction "PROGRAM_57") (pintype "bidirectional"))
    )
    (net (code "147") (name "unconnected-(TEENSY4.1A-RESET-Pad58)") (class "Default")
      (node (ref "TEENSY4.1") (pin "58") (pinfunction "RESET_58") (pintype "bidirectional"))
    )
  )
)
